# Precision_Singleboard_Leonardo_Charliepl.net
KiCad netlist of a schematic drawn in EAGLE
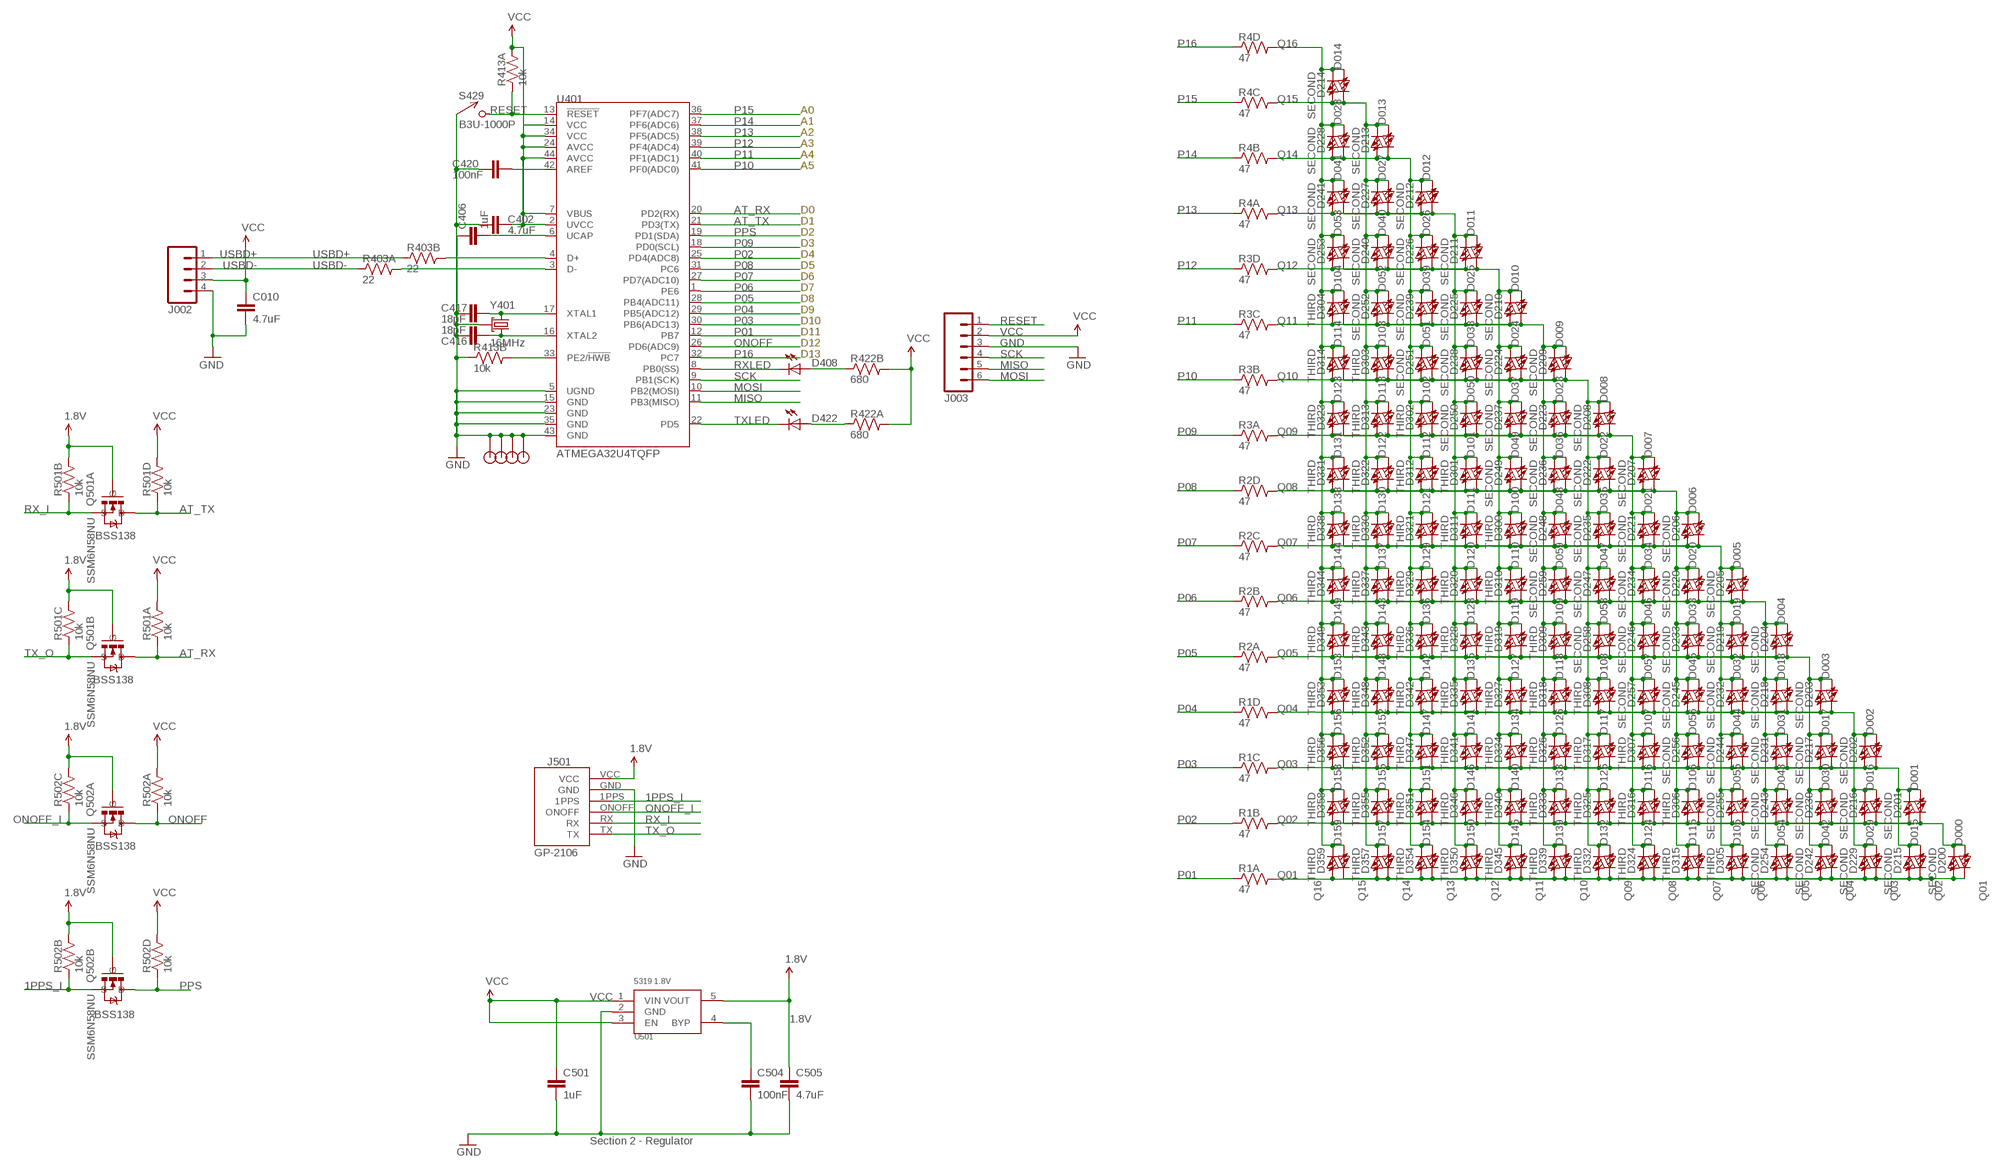
[diagram p0: schematic, sheet 1]

(export (version "E")
  (design (tool "Eeschema 10.0.6"))
  (components
    (comp (ref "C010")
      (value "4.7uF")
      (footprint "eagle-import:0603-CAP")
      (libsource (lib "eagle-import") (part "CAP0603-CAP"))
    )
    (comp (ref "C402")
      (value "4.7uF")
      (footprint "eagle-import:0603-CAP")
      (libsource (lib "eagle-import") (part "CAP0603-CAP"))
    )
    (comp (ref "C406")
      (value "1uF")
      (footprint "eagle-import:0603-CAP")
      (libsource (lib "eagle-import") (part "SparkFun-Passives_CAP0603-CAP"))
    )
    (comp (ref "C416")
      (value "18pF")
      (footprint "eagle-import:0603-CAP")
      (libsource (lib "eagle-import") (part "CAP0603-CAP"))
    )
    (comp (ref "C417")
      (value "18pF")
      (footprint "eagle-import:0603-CAP")
      (libsource (lib "eagle-import") (part "CAP0603-CAP"))
    )
    (comp (ref "C420")
      (value "100nF")
      (footprint "eagle-import:0603-CAP")
      (libsource (lib "eagle-import") (part "CAP0603-CAP"))
    )
    (comp (ref "C501")
      (value "1uF")
      (footprint "eagle-import:0603-CAP")
      (libsource (lib "eagle-import") (part "SparkFun-Passives_CAP0603-CAP"))
    )
    (comp (ref "C504")
      (value "100nF")
      (footprint "eagle-import:0603-CAP")
      (libsource (lib "eagle-import") (part "SparkFun-Passives_CAP0603-CAP"))
    )
    (comp (ref "C505")
      (value "4.7uF")
      (footprint "eagle-import:0603-CAP")
      (libsource (lib "eagle-import") (part "SparkFun-Passives_CAP0603-CAP"))
    )
    (comp (ref "D000")
      (value "HOUR")
      (footprint "eagle-import:LED-0603")
      (libsource (lib "eagle-import") (part "LED0603"))
    )
    (comp (ref "D001")
      (value "HOUR")
      (footprint "eagle-import:LED-0603")
      (libsource (lib "eagle-import") (part "LED0603"))
    )
    (comp (ref "D002")
      (value "HOUR")
      (footprint "eagle-import:LED-0603")
      (libsource (lib "eagle-import") (part "LED0603"))
    )
    (comp (ref "D003")
      (value "HOUR")
      (footprint "eagle-import:LED-0603")
      (libsource (lib "eagle-import") (part "LED0603"))
    )
    (comp (ref "D004")
      (value "HOUR")
      (footprint "eagle-import:LED-0603")
      (libsource (lib "eagle-import") (part "LED0603"))
    )
    (comp (ref "D005")
      (value "HOUR")
      (footprint "eagle-import:LED-0603")
      (libsource (lib "eagle-import") (part "LED0603"))
    )
    (comp (ref "D006")
      (value "HOUR")
      (footprint "eagle-import:LED-0603")
      (libsource (lib "eagle-import") (part "LED0603"))
    )
    (comp (ref "D007")
      (value "HOUR")
      (footprint "eagle-import:LED-0603")
      (libsource (lib "eagle-import") (part "LED0603"))
    )
    (comp (ref "D008")
      (value "HOUR")
      (footprint "eagle-import:LED-0603")
      (libsource (lib "eagle-import") (part "LED0603"))
    )
    (comp (ref "D009")
      (value "HOUR")
      (footprint "eagle-import:LED-0603")
      (libsource (lib "eagle-import") (part "LED0603"))
    )
    (comp (ref "D010")
      (value "HOUR")
      (footprint "eagle-import:LED-0603")
      (libsource (lib "eagle-import") (part "LED0603"))
    )
    (comp (ref "D011")
      (value "HOUR")
      (footprint "eagle-import:LED-0603")
      (libsource (lib "eagle-import") (part "LED0603"))
    )
    (comp (ref "D012")
      (value "HOUR")
      (footprint "eagle-import:LED-0603")
      (libsource (lib "eagle-import") (part "LED0603"))
    )
    (comp (ref "D013")
      (value "HOUR")
      (footprint "eagle-import:LED-0603")
      (libsource (lib "eagle-import") (part "LED0603"))
    )
    (comp (ref "D014")
      (value "HOUR")
      (footprint "eagle-import:LED-0603")
      (libsource (lib "eagle-import") (part "LED0603"))
    )
    (comp (ref "D015")
      (value "HOUR")
      (footprint "eagle-import:LED-0603")
      (libsource (lib "eagle-import") (part "LED0603"))
    )
    (comp (ref "D016")
      (value "HOUR")
      (footprint "eagle-import:LED-0603")
      (libsource (lib "eagle-import") (part "LED0603"))
    )
    (comp (ref "D017")
      (value "HOUR")
      (footprint "eagle-import:LED-0603")
      (libsource (lib "eagle-import") (part "LED0603"))
    )
    (comp (ref "D018")
      (value "HOUR")
      (footprint "eagle-import:LED-0603")
      (libsource (lib "eagle-import") (part "LED0603"))
    )
    (comp (ref "D019")
      (value "HOUR")
      (footprint "eagle-import:LED-0603")
      (libsource (lib "eagle-import") (part "LED0603"))
    )
    (comp (ref "D020")
      (value "HOUR")
      (footprint "eagle-import:LED-0603")
      (libsource (lib "eagle-import") (part "LED0603"))
    )
    (comp (ref "D021")
      (value "HOUR")
      (footprint "eagle-import:LED-0603")
      (libsource (lib "eagle-import") (part "LED0603"))
    )
    (comp (ref "D022")
      (value "HOUR")
      (footprint "eagle-import:LED-0603")
      (libsource (lib "eagle-import") (part "LED0603"))
    )
    (comp (ref "D023")
      (value "HOUR")
      (footprint "eagle-import:LED-0603")
      (libsource (lib "eagle-import") (part "LED0603"))
    )
    (comp (ref "D024")
      (value "HOUR")
      (footprint "eagle-import:LED-0603")
      (libsource (lib "eagle-import") (part "LED0603"))
    )
    (comp (ref "D025")
      (value "HOUR")
      (footprint "eagle-import:LED-0603")
      (libsource (lib "eagle-import") (part "LED0603"))
    )
    (comp (ref "D026")
      (value "HOUR")
      (footprint "eagle-import:LED-0603")
      (libsource (lib "eagle-import") (part "LED0603"))
    )
    (comp (ref "D027")
      (value "HOUR")
      (footprint "eagle-import:LED-0603")
      (libsource (lib "eagle-import") (part "LED0603"))
    )
    (comp (ref "D028")
      (value "HOUR")
      (footprint "eagle-import:LED-0603")
      (libsource (lib "eagle-import") (part "LED0603"))
    )
    (comp (ref "D029")
      (value "HOUR")
      (footprint "eagle-import:LED-0603")
      (libsource (lib "eagle-import") (part "LED0603"))
    )
    (comp (ref "D030")
      (value "HOUR")
      (footprint "eagle-import:LED-0603")
      (libsource (lib "eagle-import") (part "LED0603"))
    )
    (comp (ref "D031")
      (value "HOUR")
      (footprint "eagle-import:LED-0603")
      (libsource (lib "eagle-import") (part "LED0603"))
    )
    (comp (ref "D032")
      (value "HOUR")
      (footprint "eagle-import:LED-0603")
      (libsource (lib "eagle-import") (part "LED0603"))
    )
    (comp (ref "D033")
      (value "HOUR")
      (footprint "eagle-import:LED-0603")
      (libsource (lib "eagle-import") (part "LED0603"))
    )
    (comp (ref "D034")
      (value "HOUR")
      (footprint "eagle-import:LED-0603")
      (libsource (lib "eagle-import") (part "LED0603"))
    )
    (comp (ref "D035")
      (value "HOUR")
      (footprint "eagle-import:LED-0603")
      (libsource (lib "eagle-import") (part "LED0603"))
    )
    (comp (ref "D036")
      (value "HOUR")
      (footprint "eagle-import:LED-0603")
      (libsource (lib "eagle-import") (part "LED0603"))
    )
    (comp (ref "D037")
      (value "HOUR")
      (footprint "eagle-import:LED-0603")
      (libsource (lib "eagle-import") (part "LED0603"))
    )
    (comp (ref "D038")
      (value "HOUR")
      (footprint "eagle-import:LED-0603")
      (libsource (lib "eagle-import") (part "LED0603"))
    )
    (comp (ref "D039")
      (value "HOUR")
      (footprint "eagle-import:LED-0603")
      (libsource (lib "eagle-import") (part "LED0603"))
    )
    (comp (ref "D040")
      (value "HOUR")
      (footprint "eagle-import:LED-0603")
      (libsource (lib "eagle-import") (part "LED0603"))
    )
    (comp (ref "D041")
      (value "HOUR")
      (footprint "eagle-import:LED-0603")
      (libsource (lib "eagle-import") (part "LED0603"))
    )
    (comp (ref "D042")
      (value "HOUR")
      (footprint "eagle-import:LED-0603")
      (libsource (lib "eagle-import") (part "LED0603"))
    )
    (comp (ref "D043")
      (value "HOUR")
      (footprint "eagle-import:LED-0603")
      (libsource (lib "eagle-import") (part "LED0603"))
    )
    (comp (ref "D044")
      (value "HOUR")
      (footprint "eagle-import:LED-0603")
      (libsource (lib "eagle-import") (part "LED0603"))
    )
    (comp (ref "D045")
      (value "HOUR")
      (footprint "eagle-import:LED-0603")
      (libsource (lib "eagle-import") (part "LED0603"))
    )
    (comp (ref "D046")
      (value "HOUR")
      (footprint "eagle-import:LED-0603")
      (libsource (lib "eagle-import") (part "LED0603"))
    )
    (comp (ref "D047")
      (value "HOUR")
      (footprint "eagle-import:LED-0603")
      (libsource (lib "eagle-import") (part "LED0603"))
    )
    (comp (ref "D048")
      (value "HOUR")
      (footprint "eagle-import:LED-0603")
      (libsource (lib "eagle-import") (part "LED0603"))
    )
    (comp (ref "D049")
      (value "HOUR")
      (footprint "eagle-import:LED-0603")
      (libsource (lib "eagle-import") (part "LED0603"))
    )
    (comp (ref "D050")
      (value "HOUR")
      (footprint "eagle-import:LED-0603")
      (libsource (lib "eagle-import") (part "LED0603"))
    )
    (comp (ref "D051")
      (value "HOUR")
      (footprint "eagle-import:LED-0603")
      (libsource (lib "eagle-import") (part "LED0603"))
    )
    (comp (ref "D052")
      (value "HOUR")
      (footprint "eagle-import:LED-0603")
      (libsource (lib "eagle-import") (part "LED0603"))
    )
    (comp (ref "D053")
      (value "HOUR")
      (footprint "eagle-import:LED-0603")
      (libsource (lib "eagle-import") (part "LED0603"))
    )
    (comp (ref "D054")
      (value "HOUR")
      (footprint "eagle-import:LED-0603")
      (libsource (lib "eagle-import") (part "LED0603"))
    )
    (comp (ref "D055")
      (value "HOUR")
      (footprint "eagle-import:LED-0603")
      (libsource (lib "eagle-import") (part "LED0603"))
    )
    (comp (ref "D056")
      (value "HOUR")
      (footprint "eagle-import:LED-0603")
      (libsource (lib "eagle-import") (part "LED0603"))
    )
    (comp (ref "D057")
      (value "HOUR")
      (footprint "eagle-import:LED-0603")
      (libsource (lib "eagle-import") (part "LED0603"))
    )
    (comp (ref "D058")
      (value "HOUR")
      (footprint "eagle-import:LED-0603")
      (libsource (lib "eagle-import") (part "LED0603"))
    )
    (comp (ref "D059")
      (value "HOUR")
      (footprint "eagle-import:LED-0603")
      (libsource (lib "eagle-import") (part "LED0603"))
    )
    (comp (ref "D100")
      (value "MINUTE")
      (footprint "eagle-import:LED-0603")
      (libsource (lib "eagle-import") (part "LED0603"))
    )
    (comp (ref "D101")
      (value "MINUTE")
      (footprint "eagle-import:LED-0603")
      (libsource (lib "eagle-import") (part "LED0603"))
    )
    (comp (ref "D102")
      (value "MINUTE")
      (footprint "eagle-import:LED-0603")
      (libsource (lib "eagle-import") (part "LED0603"))
    )
    (comp (ref "D103")
      (value "MINUTE")
      (footprint "eagle-import:LED-0603")
      (libsource (lib "eagle-import") (part "LED0603"))
    )
    (comp (ref "D104")
      (value "MINUTE")
      (footprint "eagle-import:LED-0603")
      (libsource (lib "eagle-import") (part "LED0603"))
    )
    (comp (ref "D105")
      (value "MINUTE")
      (footprint "eagle-import:LED-0603")
      (libsource (lib "eagle-import") (part "LED0603"))
    )
    (comp (ref "D106")
      (value "MINUTE")
      (footprint "eagle-import:LED-0603")
      (libsource (lib "eagle-import") (part "LED0603"))
    )
    (comp (ref "D107")
      (value "MINUTE")
      (footprint "eagle-import:LED-0603")
      (libsource (lib "eagle-import") (part "LED0603"))
    )
    (comp (ref "D108")
      (value "MINUTE")
      (footprint "eagle-import:LED-0603")
      (libsource (lib "eagle-import") (part "LED0603"))
    )
    (comp (ref "D109")
      (value "MINUTE")
      (footprint "eagle-import:LED-0603")
      (libsource (lib "eagle-import") (part "LED0603"))
    )
    (comp (ref "D110")
      (value "MINUTE")
      (footprint "eagle-import:LED-0603")
      (libsource (lib "eagle-import") (part "LED0603"))
    )
    (comp (ref "D111")
      (value "MINUTE")
      (footprint "eagle-import:LED-0603")
      (libsource (lib "eagle-import") (part "LED0603"))
    )
    (comp (ref "D112")
      (value "MINUTE")
      (footprint "eagle-import:LED-0603")
      (libsource (lib "eagle-import") (part "LED0603"))
    )
    (comp (ref "D113")
      (value "MINUTE")
      (footprint "eagle-import:LED-0603")
      (libsource (lib "eagle-import") (part "LED0603"))
    )
    (comp (ref "D114")
      (value "MINUTE")
      (footprint "eagle-import:LED-0603")
      (libsource (lib "eagle-import") (part "LED0603"))
    )
    (comp (ref "D115")
      (value "MINUTE")
      (footprint "eagle-import:LED-0603")
      (libsource (lib "eagle-import") (part "LED0603"))
    )
    (comp (ref "D116")
      (value "MINUTE")
      (footprint "eagle-import:LED-0603")
      (libsource (lib "eagle-import") (part "LED0603"))
    )
    (comp (ref "D117")
      (value "MINUTE")
      (footprint "eagle-import:LED-0603")
      (libsource (lib "eagle-import") (part "LED0603"))
    )
    (comp (ref "D118")
      (value "MINUTE")
      (footprint "eagle-import:LED-0603")
      (libsource (lib "eagle-import") (part "LED0603"))
    )
    (comp (ref "D119")
      (value "MINUTE")
      (footprint "eagle-import:LED-0603")
      (libsource (lib "eagle-import") (part "LED0603"))
    )
    (comp (ref "D120")
      (value "MINUTE")
      (footprint "eagle-import:LED-0603")
      (libsource (lib "eagle-import") (part "LED0603"))
    )
    (comp (ref "D121")
      (value "MINUTE")
      (footprint "eagle-import:LED-0603")
      (libsource (lib "eagle-import") (part "LED0603"))
    )
    (comp (ref "D122")
      (value "MINUTE")
      (footprint "eagle-import:LED-0603")
      (libsource (lib "eagle-import") (part "LED0603"))
    )
    (comp (ref "D123")
      (value "MINUTE")
      (footprint "eagle-import:LED-0603")
      (libsource (lib "eagle-import") (part "LED0603"))
    )
    (comp (ref "D124")
      (value "MINUTE")
      (footprint "eagle-import:LED-0603")
      (libsource (lib "eagle-import") (part "LED0603"))
    )
    (comp (ref "D125")
      (value "MINUTE")
      (footprint "eagle-import:LED-0603")
      (libsource (lib "eagle-import") (part "LED0603"))
    )
    (comp (ref "D126")
      (value "MINUTE")
      (footprint "eagle-import:LED-0603")
      (libsource (lib "eagle-import") (part "LED0603"))
    )
    (comp (ref "D127")
      (value "MINUTE")
      (footprint "eagle-import:LED-0603")
      (libsource (lib "eagle-import") (part "LED0603"))
    )
    (comp (ref "D128")
      (value "MINUTE")
      (footprint "eagle-import:LED-0603")
      (libsource (lib "eagle-import") (part "LED0603"))
    )
    (comp (ref "D129")
      (value "MINUTE")
      (footprint "eagle-import:LED-0603")
      (libsource (lib "eagle-import") (part "LED0603"))
    )
    (comp (ref "D130")
      (value "MINUTE")
      (footprint "eagle-import:LED-0603")
      (libsource (lib "eagle-import") (part "LED0603"))
    )
    (comp (ref "D131")
      (value "MINUTE")
      (footprint "eagle-import:LED-0603")
      (libsource (lib "eagle-import") (part "LED0603"))
    )
    (comp (ref "D132")
      (value "MINUTE")
      (footprint "eagle-import:LED-0603")
      (libsource (lib "eagle-import") (part "LED0603"))
    )
    (comp (ref "D133")
      (value "MINUTE")
      (footprint "eagle-import:LED-0603")
      (libsource (lib "eagle-import") (part "LED0603"))
    )
    (comp (ref "D134")
      (value "MINUTE")
      (footprint "eagle-import:LED-0603")
      (libsource (lib "eagle-import") (part "LED0603"))
    )
    (comp (ref "D135")
      (value "MINUTE")
      (footprint "eagle-import:LED-0603")
      (libsource (lib "eagle-import") (part "LED0603"))
    )
    (comp (ref "D136")
      (value "MINUTE")
      (footprint "eagle-import:LED-0603")
      (libsource (lib "eagle-import") (part "LED0603"))
    )
    (comp (ref "D137")
      (value "MINUTE")
      (footprint "eagle-import:LED-0603")
      (libsource (lib "eagle-import") (part "LED0603"))
    )
    (comp (ref "D138")
      (value "MINUTE")
      (footprint "eagle-import:LED-0603")
      (libsource (lib "eagle-import") (part "LED0603"))
    )
    (comp (ref "D139")
      (value "MINUTE")
      (footprint "eagle-import:LED-0603")
      (libsource (lib "eagle-import") (part "LED0603"))
    )
    (comp (ref "D140")
      (value "MINUTE")
      (footprint "eagle-import:LED-0603")
      (libsource (lib "eagle-import") (part "LED0603"))
    )
    (comp (ref "D141")
      (value "MINUTE")
      (footprint "eagle-import:LED-0603")
      (libsource (lib "eagle-import") (part "LED0603"))
    )
    (comp (ref "D142")
      (value "MINUTE")
      (footprint "eagle-import:LED-0603")
      (libsource (lib "eagle-import") (part "LED0603"))
    )
    (comp (ref "D143")
      (value "MINUTE")
      (footprint "eagle-import:LED-0603")
      (libsource (lib "eagle-import") (part "LED0603"))
    )
    (comp (ref "D144")
      (value "MINUTE")
      (footprint "eagle-import:LED-0603")
      (libsource (lib "eagle-import") (part "LED0603"))
    )
    (comp (ref "D145")
      (value "MINUTE")
      (footprint "eagle-import:LED-0603")
      (libsource (lib "eagle-import") (part "LED0603"))
    )
    (comp (ref "D146")
      (value "MINUTE")
      (footprint "eagle-import:LED-0603")
      (libsource (lib "eagle-import") (part "LED0603"))
    )
    (comp (ref "D147")
      (value "MINUTE")
      (footprint "eagle-import:LED-0603")
      (libsource (lib "eagle-import") (part "LED0603"))
    )
    (comp (ref "D148")
      (value "MINUTE")
      (footprint "eagle-import:LED-0603")
      (libsource (lib "eagle-import") (part "LED0603"))
    )
    (comp (ref "D149")
      (value "MINUTE")
      (footprint "eagle-import:LED-0603")
      (libsource (lib "eagle-import") (part "LED0603"))
    )
    (comp (ref "D150")
      (value "MINUTE")
      (footprint "eagle-import:LED-0603")
      (libsource (lib "eagle-import") (part "LED0603"))
    )
    (comp (ref "D151")
      (value "MINUTE")
      (footprint "eagle-import:LED-0603")
      (libsource (lib "eagle-import") (part "LED0603"))
    )
    (comp (ref "D152")
      (value "MINUTE")
      (footprint "eagle-import:LED-0603")
      (libsource (lib "eagle-import") (part "LED0603"))
    )
    (comp (ref "D153")
      (value "MINUTE")
      (footprint "eagle-import:LED-0603")
      (libsource (lib "eagle-import") (part "LED0603"))
    )
    (comp (ref "D154")
      (value "MINUTE")
      (footprint "eagle-import:LED-0603")
      (libsource (lib "eagle-import") (part "LED0603"))
    )
    (comp (ref "D155")
      (value "MINUTE")
      (footprint "eagle-import:LED-0603")
      (libsource (lib "eagle-import") (part "LED0603"))
    )
    (comp (ref "D156")
      (value "MINUTE")
      (footprint "eagle-import:LED-0603")
      (libsource (lib "eagle-import") (part "LED0603"))
    )
    (comp (ref "D157")
      (value "MINUTE")
      (footprint "eagle-import:LED-0603")
      (libsource (lib "eagle-import") (part "LED0603"))
    )
    (comp (ref "D158")
      (value "MINUTE")
      (footprint "eagle-import:LED-0603")
      (libsource (lib "eagle-import") (part "LED0603"))
    )
    (comp (ref "D159")
      (value "MINUTE")
      (footprint "eagle-import:LED-0603")
      (libsource (lib "eagle-import") (part "LED0603"))
    )
    (comp (ref "D200")
      (value "SECOND")
      (footprint "eagle-import:LED-0603")
      (libsource (lib "eagle-import") (part "SparkFun-LED_LED0603"))
    )
    (comp (ref "D201")
      (value "SECOND")
      (footprint "eagle-import:LED-0603")
      (libsource (lib "eagle-import") (part "SparkFun-LED_LED0603"))
    )
    (comp (ref "D202")
      (value "SECOND")
      (footprint "eagle-import:LED-0603")
      (libsource (lib "eagle-import") (part "SparkFun-LED_LED0603"))
    )
    (comp (ref "D203")
      (value "SECOND")
      (footprint "eagle-import:LED-0603")
      (libsource (lib "eagle-import") (part "SparkFun-LED_LED0603"))
    )
    (comp (ref "D204")
      (value "SECOND")
      (footprint "eagle-import:LED-0603")
      (libsource (lib "eagle-import") (part "SparkFun-LED_LED0603"))
    )
    (comp (ref "D205")
      (value "SECOND")
      (footprint "eagle-import:LED-0603")
      (libsource (lib "eagle-import") (part "SparkFun-LED_LED0603"))
    )
    (comp (ref "D206")
      (value "SECOND")
      (footprint "eagle-import:LED-0603")
      (libsource (lib "eagle-import") (part "SparkFun-LED_LED0603"))
    )
    (comp (ref "D207")
      (value "SECOND")
      (footprint "eagle-import:LED-0603")
      (libsource (lib "eagle-import") (part "SparkFun-LED_LED0603"))
    )
    (comp (ref "D208")
      (value "SECOND")
      (footprint "eagle-import:LED-0603")
      (libsource (lib "eagle-import") (part "SparkFun-LED_LED0603"))
    )
    (comp (ref "D209")
      (value "SECOND")
      (footprint "eagle-import:LED-0603")
      (libsource (lib "eagle-import") (part "SparkFun-LED_LED0603"))
    )
    (comp (ref "D210")
      (value "SECOND")
      (footprint "eagle-import:LED-0603")
      (libsource (lib "eagle-import") (part "SparkFun-LED_LED0603"))
    )
    (comp (ref "D211")
      (value "SECOND")
      (footprint "eagle-import:LED-0603")
      (libsource (lib "eagle-import") (part "SparkFun-LED_LED0603"))
    )
    (comp (ref "D212")
      (value "SECOND")
      (footprint "eagle-import:LED-0603")
      (libsource (lib "eagle-import") (part "SparkFun-LED_LED0603"))
    )
    (comp (ref "D213")
      (value "SECOND")
      (footprint "eagle-import:LED-0603")
      (libsource (lib "eagle-import") (part "SparkFun-LED_LED0603"))
    )
    (comp (ref "D214")
      (value "SECOND")
      (footprint "eagle-import:LED-0603")
      (libsource (lib "eagle-import") (part "SparkFun-LED_LED0603"))
    )
    (comp (ref "D215")
      (value "SECOND")
      (footprint "eagle-import:LED-0603")
      (libsource (lib "eagle-import") (part "SparkFun-LED_LED0603"))
    )
    (comp (ref "D216")
      (value "SECOND")
      (footprint "eagle-import:LED-0603")
      (libsource (lib "eagle-import") (part "SparkFun-LED_LED0603"))
    )
    (comp (ref "D217")
      (value "SECOND")
      (footprint "eagle-import:LED-0603")
      (libsource (lib "eagle-import") (part "SparkFun-LED_LED0603"))
    )
    (comp (ref "D218")
      (value "SECOND")
      (footprint "eagle-import:LED-0603")
      (libsource (lib "eagle-import") (part "SparkFun-LED_LED0603"))
    )
    (comp (ref "D219")
      (value "SECOND")
      (footprint "eagle-import:LED-0603")
      (libsource (lib "eagle-import") (part "SparkFun-LED_LED0603"))
    )
    (comp (ref "D220")
      (value "SECOND")
      (footprint "eagle-import:LED-0603")
      (libsource (lib "eagle-import") (part "SparkFun-LED_LED0603"))
    )
    (comp (ref "D221")
      (value "SECOND")
      (footprint "eagle-import:LED-0603")
      (libsource (lib "eagle-import") (part "SparkFun-LED_LED0603"))
    )
    (comp (ref "D222")
      (value "SECOND")
      (footprint "eagle-import:LED-0603")
      (libsource (lib "eagle-import") (part "SparkFun-LED_LED0603"))
    )
    (comp (ref "D223")
      (value "SECOND")
      (footprint "eagle-import:LED-0603")
      (libsource (lib "eagle-import") (part "SparkFun-LED_LED0603"))
    )
    (comp (ref "D224")
      (value "SECOND")
      (footprint "eagle-import:LED-0603")
      (libsource (lib "eagle-import") (part "SparkFun-LED_LED0603"))
    )
    (comp (ref "D225")
      (value "SECOND")
      (footprint "eagle-import:LED-0603")
      (libsource (lib "eagle-import") (part "SparkFun-LED_LED0603"))
    )
    (comp (ref "D226")
      (value "SECOND")
      (footprint "eagle-import:LED-0603")
      (libsource (lib "eagle-import") (part "SparkFun-LED_LED0603"))
    )
    (comp (ref "D227")
      (value "SECOND")
      (footprint "eagle-import:LED-0603")
      (libsource (lib "eagle-import") (part "SparkFun-LED_LED0603"))
    )
    (comp (ref "D228")
      (value "SECOND")
      (footprint "eagle-import:LED-0603")
      (libsource (lib "eagle-import") (part "SparkFun-LED_LED0603"))
    )
    (comp (ref "D229")
      (value "SECOND")
      (footprint "eagle-import:LED-0603")
      (libsource (lib "eagle-import") (part "SparkFun-LED_LED0603"))
    )
    (comp (ref "D230")
      (value "SECOND")
      (footprint "eagle-import:LED-0603")
      (libsource (lib "eagle-import") (part "SparkFun-LED_LED0603"))
    )
    (comp (ref "D231")
      (value "SECOND")
      (footprint "eagle-import:LED-0603")
      (libsource (lib "eagle-import") (part "SparkFun-LED_LED0603"))
    )
    (comp (ref "D232")
      (value "SECOND")
      (footprint "eagle-import:LED-0603")
      (libsource (lib "eagle-import") (part "SparkFun-LED_LED0603"))
    )
    (comp (ref "D233")
      (value "SECOND")
      (footprint "eagle-import:LED-0603")
      (libsource (lib "eagle-import") (part "SparkFun-LED_LED0603"))
    )
    (comp (ref "D234")
      (value "SECOND")
      (footprint "eagle-import:LED-0603")
      (libsource (lib "eagle-import") (part "SparkFun-LED_LED0603"))
    )
    (comp (ref "D235")
      (value "SECOND")
      (footprint "eagle-import:LED-0603")
      (libsource (lib "eagle-import") (part "SparkFun-LED_LED0603"))
    )
    (comp (ref "D236")
      (value "SECOND")
      (footprint "eagle-import:LED-0603")
      (libsource (lib "eagle-import") (part "SparkFun-LED_LED0603"))
    )
    (comp (ref "D237")
      (value "SECOND")
      (footprint "eagle-import:LED-0603")
      (libsource (lib "eagle-import") (part "SparkFun-LED_LED0603"))
    )
    (comp (ref "D238")
      (value "SECOND")
      (footprint "eagle-import:LED-0603")
      (libsource (lib "eagle-import") (part "SparkFun-LED_LED0603"))
    )
    (comp (ref "D239")
      (value "SECOND")
      (footprint "eagle-import:LED-0603")
      (libsource (lib "eagle-import") (part "SparkFun-LED_LED0603"))
    )
    (comp (ref "D240")
      (value "SECOND")
      (footprint "eagle-import:LED-0603")
      (libsource (lib "eagle-import") (part "SparkFun-LED_LED0603"))
    )
    (comp (ref "D241")
      (value "SECOND")
      (footprint "eagle-import:LED-0603")
      (libsource (lib "eagle-import") (part "LED0603"))
    )
    (comp (ref "D242")
      (value "SECOND")
      (footprint "eagle-import:LED-0603")
      (libsource (lib "eagle-import") (part "SparkFun-LED_LED0603"))
    )
    (comp (ref "D243")
      (value "SECOND")
      (footprint "eagle-import:LED-0603")
      (libsource (lib "eagle-import") (part "SparkFun-LED_LED0603"))
    )
    (comp (ref "D244")
      (value "SECOND")
      (footprint "eagle-import:LED-0603")
      (libsource (lib "eagle-import") (part "SparkFun-LED_LED0603"))
    )
    (comp (ref "D245")
      (value "SECOND")
      (footprint "eagle-import:LED-0603")
      (libsource (lib "eagle-import") (part "SparkFun-LED_LED0603"))
    )
    (comp (ref "D246")
      (value "SECOND")
      (footprint "eagle-import:LED-0603")
      (libsource (lib "eagle-import") (part "SparkFun-LED_LED0603"))
    )
    (comp (ref "D247")
      (value "SECOND")
      (footprint "eagle-import:LED-0603")
      (libsource (lib "eagle-import") (part "SparkFun-LED_LED0603"))
    )
    (comp (ref "D248")
      (value "SECOND")
      (footprint "eagle-import:LED-0603")
      (libsource (lib "eagle-import") (part "SparkFun-LED_LED0603"))
    )
    (comp (ref "D249")
      (value "SECOND")
      (footprint "eagle-import:LED-0603")
      (libsource (lib "eagle-import") (part "SparkFun-LED_LED0603"))
    )
    (comp (ref "D250")
      (value "SECOND")
      (footprint "eagle-import:LED-0603")
      (libsource (lib "eagle-import") (part "SparkFun-LED_LED0603"))
    )
    (comp (ref "D251")
      (value "SECOND")
      (footprint "eagle-import:LED-0603")
      (libsource (lib "eagle-import") (part "SparkFun-LED_LED0603"))
    )
    (comp (ref "D252")
      (value "SECOND")
      (footprint "eagle-import:LED-0603")
      (libsource (lib "eagle-import") (part "SparkFun-LED_LED0603"))
    )
    (comp (ref "D253")
      (value "SECOND")
      (footprint "eagle-import:LED-0603")
      (libsource (lib "eagle-import") (part "SparkFun-LED_LED0603"))
    )
    (comp (ref "D254")
      (value "SECOND")
      (footprint "eagle-import:LED-0603")
      (libsource (lib "eagle-import") (part "SparkFun-LED_LED0603"))
    )
    (comp (ref "D255")
      (value "SECOND")
      (footprint "eagle-import:LED-0603")
      (libsource (lib "eagle-import") (part "SparkFun-LED_LED0603"))
    )
    (comp (ref "D256")
      (value "SECOND")
      (footprint "eagle-import:LED-0603")
      (libsource (lib "eagle-import") (part "SparkFun-LED_LED0603"))
    )
    (comp (ref "D257")
      (value "SECOND")
      (footprint "eagle-import:LED-0603")
      (libsource (lib "eagle-import") (part "SparkFun-LED_LED0603"))
    )
    (comp (ref "D258")
      (value "SECOND")
      (footprint "eagle-import:LED-0603")
      (libsource (lib "eagle-import") (part "SparkFun-LED_LED0603"))
    )
    (comp (ref "D259")
      (value "SECOND")
      (footprint "eagle-import:LED-0603")
      (libsource (lib "eagle-import") (part "SparkFun-LED_LED0603"))
    )
    (comp (ref "D300")
      (value "THIRD")
      (footprint "eagle-import:LED-0603")
      (libsource (lib "eagle-import") (part "SparkFun-LED_LED0603"))
    )
    (comp (ref "D301")
      (value "THIRD")
      (footprint "eagle-import:LED-0603")
      (libsource (lib "eagle-import") (part "SparkFun-LED_LED0603"))
    )
    (comp (ref "D302")
      (value "THIRD")
      (footprint "eagle-import:LED-0603")
      (libsource (lib "eagle-import") (part "SparkFun-LED_LED0603"))
    )
    (comp (ref "D303")
      (value "THIRD")
      (footprint "eagle-import:LED-0603")
      (libsource (lib "eagle-import") (part "SparkFun-LED_LED0603"))
    )
    (comp (ref "D304")
      (value "THIRD")
      (footprint "eagle-import:LED-0603")
      (libsource (lib "eagle-import") (part "SparkFun-LED_LED0603"))
    )
    (comp (ref "D305")
      (value "THIRD")
      (footprint "eagle-import:LED-0603")
      (libsource (lib "eagle-import") (part "SparkFun-LED_LED0603"))
    )
    (comp (ref "D306")
      (value "THIRD")
      (footprint "eagle-import:LED-0603")
      (libsource (lib "eagle-import") (part "SparkFun-LED_LED0603"))
    )
    (comp (ref "D307")
      (value "THIRD")
      (footprint "eagle-import:LED-0603")
      (libsource (lib "eagle-import") (part "SparkFun-LED_LED0603"))
    )
    (comp (ref "D308")
      (value "THIRD")
      (footprint "eagle-import:LED-0603")
      (libsource (lib "eagle-import") (part "SparkFun-LED_LED0603"))
    )
    (comp (ref "D309")
      (value "THIRD")
      (footprint "eagle-import:LED-0603")
      (libsource (lib "eagle-import") (part "SparkFun-LED_LED0603"))
    )
    (comp (ref "D310")
      (value "THIRD")
      (footprint "eagle-import:LED-0603")
      (libsource (lib "eagle-import") (part "SparkFun-LED_LED0603"))
    )
    (comp (ref "D311")
      (value "THIRD")
      (footprint "eagle-import:LED-0603")
      (libsource (lib "eagle-import") (part "SparkFun-LED_LED0603"))
    )
    (comp (ref "D312")
      (value "THIRD")
      (footprint "eagle-import:LED-0603")
      (libsource (lib "eagle-import") (part "SparkFun-LED_LED0603"))
    )
    (comp (ref "D313")
      (value "THIRD")
      (footprint "eagle-import:LED-0603")
      (libsource (lib "eagle-import") (part "SparkFun-LED_LED0603"))
    )
    (comp (ref "D314")
      (value "THIRD")
      (footprint "eagle-import:LED-0603")
      (libsource (lib "eagle-import") (part "SparkFun-LED_LED0603"))
    )
    (comp (ref "D315")
      (value "THIRD")
      (footprint "eagle-import:LED-0603")
      (libsource (lib "eagle-import") (part "SparkFun-LED_LED0603"))
    )
    (comp (ref "D316")
      (value "THIRD")
      (footprint "eagle-import:LED-0603")
      (libsource (lib "eagle-import") (part "SparkFun-LED_LED0603"))
    )
    (comp (ref "D317")
      (value "THIRD")
      (footprint "eagle-import:LED-0603")
      (libsource (lib "eagle-import") (part "SparkFun-LED_LED0603"))
    )
    (comp (ref "D318")
      (value "THIRD")
      (footprint "eagle-import:LED-0603")
      (libsource (lib "eagle-import") (part "SparkFun-LED_LED0603"))
    )
    (comp (ref "D319")
      (value "THIRD")
      (footprint "eagle-import:LED-0603")
      (libsource (lib "eagle-import") (part "SparkFun-LED_LED0603"))
    )
    (comp (ref "D320")
      (value "THIRD")
      (footprint "eagle-import:LED-0603")
      (libsource (lib "eagle-import") (part "SparkFun-LED_LED0603"))
    )
    (comp (ref "D321")
      (value "THIRD")
      (footprint "eagle-import:LED-0603")
      (libsource (lib "eagle-import") (part "SparkFun-LED_LED0603"))
    )
    (comp (ref "D322")
      (value "THIRD")
      (footprint "eagle-import:LED-0603")
      (libsource (lib "eagle-import") (part "SparkFun-LED_LED0603"))
    )
    (comp (ref "D323")
      (value "THIRD")
      (footprint "eagle-import:LED-0603")
      (libsource (lib "eagle-import") (part "SparkFun-LED_LED0603"))
    )
    (comp (ref "D324")
      (value "THIRD")
      (footprint "eagle-import:LED-0603")
      (libsource (lib "eagle-import") (part "SparkFun-LED_LED0603"))
    )
    (comp (ref "D325")
      (value "THIRD")
      (footprint "eagle-import:LED-0603")
      (libsource (lib "eagle-import") (part "SparkFun-LED_LED0603"))
    )
    (comp (ref "D326")
      (value "THIRD")
      (footprint "eagle-import:LED-0603")
      (libsource (lib "eagle-import") (part "SparkFun-LED_LED0603"))
    )
    (comp (ref "D327")
      (value "THIRD")
      (footprint "eagle-import:LED-0603")
      (libsource (lib "eagle-import") (part "SparkFun-LED_LED0603"))
    )
    (comp (ref "D328")
      (value "THIRD")
      (footprint "eagle-import:LED-0603")
      (libsource (lib "eagle-import") (part "SparkFun-LED_LED0603"))
    )
    (comp (ref "D329")
      (value "THIRD")
      (footprint "eagle-import:LED-0603")
      (libsource (lib "eagle-import") (part "SparkFun-LED_LED0603"))
    )
    (comp (ref "D330")
      (value "THIRD")
      (footprint "eagle-import:LED-0603")
      (libsource (lib "eagle-import") (part "SparkFun-LED_LED0603"))
    )
    (comp (ref "D331")
      (value "THIRD")
      (footprint "eagle-import:LED-0603")
      (libsource (lib "eagle-import") (part "SparkFun-LED_LED0603"))
    )
    (comp (ref "D332")
      (value "THIRD")
      (footprint "eagle-import:LED-0603")
      (libsource (lib "eagle-import") (part "SparkFun-LED_LED0603"))
    )
    (comp (ref "D333")
      (value "THIRD")
      (footprint "eagle-import:LED-0603")
      (libsource (lib "eagle-import") (part "SparkFun-LED_LED0603"))
    )
    (comp (ref "D334")
      (value "THIRD")
      (footprint "eagle-import:LED-0603")
      (libsource (lib "eagle-import") (part "SparkFun-LED_LED0603"))
    )
    (comp (ref "D335")
      (value "THIRD")
      (footprint "eagle-import:LED-0603")
      (libsource (lib "eagle-import") (part "SparkFun-LED_LED0603"))
    )
    (comp (ref "D336")
      (value "THIRD")
      (footprint "eagle-import:LED-0603")
      (libsource (lib "eagle-import") (part "SparkFun-LED_LED0603"))
    )
    (comp (ref "D337")
      (value "THIRD")
      (footprint "eagle-import:LED-0603")
      (libsource (lib "eagle-import") (part "SparkFun-LED_LED0603"))
    )
    (comp (ref "D338")
      (value "THIRD")
      (footprint "eagle-import:LED-0603")
      (libsource (lib "eagle-import") (part "SparkFun-LED_LED0603"))
    )
    (comp (ref "D339")
      (value "THIRD")
      (footprint "eagle-import:LED-0603")
      (libsource (lib "eagle-import") (part "SparkFun-LED_LED0603"))
    )
    (comp (ref "D340")
      (value "THIRD")
      (footprint "eagle-import:LED-0603")
      (libsource (lib "eagle-import") (part "SparkFun-LED_LED0603"))
    )
    (comp (ref "D341")
      (value "THIRD")
      (footprint "eagle-import:LED-0603")
      (libsource (lib "eagle-import") (part "SparkFun-LED_LED0603"))
    )
    (comp (ref "D342")
      (value "THIRD")
      (footprint "eagle-import:LED-0603")
      (libsource (lib "eagle-import") (part "SparkFun-LED_LED0603"))
    )
    (comp (ref "D343")
      (value "THIRD")
      (footprint "eagle-import:LED-0603")
      (libsource (lib "eagle-import") (part "SparkFun-LED_LED0603"))
    )
    (comp (ref "D344")
      (value "THIRD")
      (footprint "eagle-import:LED-0603")
      (libsource (lib "eagle-import") (part "SparkFun-LED_LED0603"))
    )
    (comp (ref "D345")
      (value "THIRD")
      (footprint "eagle-import:LED-0603")
      (libsource (lib "eagle-import") (part "SparkFun-LED_LED0603"))
    )
    (comp (ref "D346")
      (value "THIRD")
      (footprint "eagle-import:LED-0603")
      (libsource (lib "eagle-import") (part "SparkFun-LED_LED0603"))
    )
    (comp (ref "D347")
      (value "THIRD")
      (footprint "eagle-import:LED-0603")
      (libsource (lib "eagle-import") (part "SparkFun-LED_LED0603"))
    )
    (comp (ref "D348")
      (value "THIRD")
      (footprint "eagle-import:LED-0603")
      (libsource (lib "eagle-import") (part "SparkFun-LED_LED0603"))
    )
    (comp (ref "D349")
      (value "THIRD")
      (footprint "eagle-import:LED-0603")
      (libsource (lib "eagle-import") (part "SparkFun-LED_LED0603"))
    )
    (comp (ref "D350")
      (value "THIRD")
      (footprint "eagle-import:LED-0603")
      (libsource (lib "eagle-import") (part "SparkFun-LED_LED0603"))
    )
    (comp (ref "D351")
      (value "THIRD")
      (footprint "eagle-import:LED-0603")
      (libsource (lib "eagle-import") (part "SparkFun-LED_LED0603"))
    )
    (comp (ref "D352")
      (value "THIRD")
      (footprint "eagle-import:LED-0603")
      (libsource (lib "eagle-import") (part "SparkFun-LED_LED0603"))
    )
    (comp (ref "D353")
      (value "THIRD")
      (footprint "eagle-import:LED-0603")
      (libsource (lib "eagle-import") (part "SparkFun-LED_LED0603"))
    )
    (comp (ref "D354")
      (value "THIRD")
      (footprint "eagle-import:LED-0603")
      (libsource (lib "eagle-import") (part "SparkFun-LED_LED0603"))
    )
    (comp (ref "D355")
      (value "THIRD")
      (footprint "eagle-import:LED-0603")
      (libsource (lib "eagle-import") (part "SparkFun-LED_LED0603"))
    )
    (comp (ref "D356")
      (value "THIRD")
      (footprint "eagle-import:LED-0603")
      (libsource (lib "eagle-import") (part "SparkFun-LED_LED0603"))
    )
    (comp (ref "D357")
      (value "THIRD")
      (footprint "eagle-import:LED-0603")
      (libsource (lib "eagle-import") (part "SparkFun-LED_LED0603"))
    )
    (comp (ref "D358")
      (value "THIRD")
      (footprint "eagle-import:LED-0603")
      (libsource (lib "eagle-import") (part "SparkFun-LED_LED0603"))
    )
    (comp (ref "D359")
      (value "THIRD")
      (footprint "eagle-import:LED-0603")
      (libsource (lib "eagle-import") (part "SparkFun-LED_LED0603"))
    )
    (comp (ref "D408")
      (value "RED")
      (footprint "eagle-import:LED-0603")
      (libsource (lib "eagle-import") (part "LED0603"))
    )
    (comp (ref "D422")
      (value "BLUE")
      (footprint "eagle-import:LED-0603")
      (libsource (lib "eagle-import") (part "LED0603"))
    )
    (comp (ref "J002")
      (value "M04PTH")
      (footprint "eagle-import:1X04")
      (libsource (lib "eagle-import") (part "M04PTH"))
    )
    (comp (ref "J003")
      (value "M06SIP")
      (footprint "eagle-import:1X06")
      (libsource (lib "eagle-import") (part "M06SIP"))
    )
    (comp (ref "J501")
      (value "GP-2106")
      (footprint "eagle-import:GP-2106")
      (libsource (lib "eagle-import") (part "GP-2106"))
    )
    (comp (ref "JP1")
      (value "STANDOFF")
      (footprint "eagle-import:STANDOFF")
      (libsource (lib "eagle-import") (part "STANDOFF"))
    )
    (comp (ref "JP2")
      (value "STANDOFF")
      (footprint "eagle-import:STANDOFF")
      (libsource (lib "eagle-import") (part "STANDOFF"))
    )
    (comp (ref "JP3")
      (value "STANDOFF")
      (footprint "eagle-import:STANDOFF")
      (libsource (lib "eagle-import") (part "STANDOFF"))
    )
    (comp (ref "JP4")
      (value "STANDOFF")
      (footprint "eagle-import:STANDOFF")
      (libsource (lib "eagle-import") (part "STANDOFF"))
    )
    (comp (ref "Q501")
      (value "SSM6N58NU")
      (footprint "eagle-import:UDFN6")
      (libsource (lib "eagle-import") (part "SSM6N58NU"))
    )
    (comp (ref "Q502")
      (value "SSM6N58NU")
      (footprint "eagle-import:UDFN6")
      (libsource (lib "eagle-import") (part "SSM6N58NU"))
    )
    (comp (ref "R1")
      (value "47")
      (footprint "eagle-import:CRA04")
      (libsource (lib "eagle-import") (part "RP404"))
    )
    (comp (ref "R2")
      (value "47")
      (footprint "eagle-import:CRA04")
      (libsource (lib "eagle-import") (part "RP404"))
    )
    (comp (ref "R3")
      (value "47")
      (footprint "eagle-import:CRA04")
      (libsource (lib "eagle-import") (part "RP404"))
    )
    (comp (ref "R4")
      (value "47")
      (footprint "eagle-import:CRA04")
      (libsource (lib "eagle-import") (part "RP404"))
    )
    (comp (ref "R403")
      (value "22")
      (footprint "eagle-import:CRA02")
      (libsource (lib "eagle-import") (part "RP2EXB24V"))
    )
    (comp (ref "R413")
      (value "10k")
      (footprint "eagle-import:CRA02")
      (libsource (lib "eagle-import") (part "RP2EXB24V"))
    )
    (comp (ref "R422")
      (value "680")
      (footprint "eagle-import:CRA02")
      (libsource (lib "eagle-import") (part "RP2EXB24V"))
    )
    (comp (ref "R501")
      (value "10k")
      (footprint "eagle-import:CRA04")
      (fields (field (name "DIGIKEY") "CRA4S810KCT-ND"))
      (libsource (lib "eagle-import") (part "RP404"))
    )
    (comp (ref "R502")
      (value "10k")
      (footprint "eagle-import:CRA04")
      (fields (field (name "DIGIKEY") "CRA4S810KCT-ND"))
      (libsource (lib "eagle-import") (part "RP404"))
    )
    (comp (ref "S429")
      (value "B3U-1000P")
      (footprint "eagle-import:B3U-1000P")
      (libsource (lib "eagle-import") (part "B3U-1000P"))
    )
    (comp (ref "U401")
      (value "ATMEGA32U4TQFP")
      (footprint "eagle-import:SPARKFUN-DIGITALIC_TQFP44")
      (libsource (lib "eagle-import") (part "ATMEGA32U4TQFP"))
    )
    (comp (ref "U501")
      (value "5319 1.8V")
      (footprint "eagle-import:SOT-23-5")
      (libsource (lib "eagle-import") (part "MIC5319D5"))
    )
    (comp (ref "Y401")
      (value "16MHz")
      (footprint "eagle-import:CRYSTAL_SMD")
      (libsource (lib "eagle-import") (part "TSX-3225"))
    )
  )
  (nets
    (net (code "1") (name "/1PPS_I") (class "Default")
      (node (ref "J501") (pin "1PPS") (pinfunction "1PPS_1PPS") (pintype "bidirectional"))
      (node (ref "Q502") (pin "4") (pinfunction "S_4") (pintype "passive"))
      (node (ref "R502") (pin "2") (pinfunction "1_2") (pintype "passive"))
    )
    (net (code "2") (name "/AT_RX") (class "Default")
      (node (ref "Q501") (pin "3") (pinfunction "D_3") (pintype "passive"))
      (node (ref "R501") (pin "1") (pinfunction "1_1") (pintype "passive"))
      (node (ref "U401") (pin "20") (pinfunction "PD2(RX)_20") (pintype "bidirectional"))
    )
    (net (code "3") (name "/AT_TX") (class "Default")
      (node (ref "Q501") (pin "6") (pinfunction "D_6") (pintype "passive"))
      (node (ref "R501") (pin "4") (pinfunction "1_4") (pintype "passive"))
      (node (ref "U401") (pin "21") (pinfunction "PD3(TX)_21") (pintype "bidirectional"))
    )
    (net (code "4") (name "/MISO") (class "Default")
      (node (ref "J003") (pin "5") (pinfunction "5_5") (pintype "passive"))
      (node (ref "U401") (pin "11") (pinfunction "PB3(MISO)_11") (pintype "bidirectional"))
    )
    (net (code "5") (name "/MOSI") (class "Default")
      (node (ref "J003") (pin "6") (pinfunction "6_6") (pintype "passive"))
      (node (ref "U401") (pin "10") (pinfunction "PB2(MOSI)_10") (pintype "bidirectional"))
    )
    (net (code "6") (name "/ONOFF") (class "Default")
      (node (ref "Q502") (pin "6") (pinfunction "D_6") (pintype "passive"))
      (node (ref "R502") (pin "1") (pinfunction "1_1") (pintype "passive"))
      (node (ref "U401") (pin "26") (pinfunction "PD6(ADC9)_26") (pintype "bidirectional"))
    )
    (net (code "7") (name "/ONOFF_I") (class "Default")
      (node (ref "J501") (pin "ONOFF") (pinfunction "ONOFF_ONOFF") (pintype "bidirectional"))
      (node (ref "Q502") (pin "1") (pinfunction "S_1") (pintype "passive"))
      (node (ref "R502") (pin "3") (pinfunction "1_3") (pintype "passive"))
    )
    (net (code "8") (name "/P01") (class "Default")
      (node (ref "R1") (pin "1") (pinfunction "1_1") (pintype "passive"))
      (node (ref "U401") (pin "12") (pinfunction "PB7_12") (pintype "bidirectional"))
    )
    (net (code "9") (name "/P02") (class "Default")
      (node (ref "R1") (pin "2") (pinfunction "1_2") (pintype "passive"))
      (node (ref "U401") (pin "25") (pinfunction "PD4(ADC8)_25") (pintype "bidirectional"))
    )
    (net (code "10") (name "/P03") (class "Default")
      (node (ref "R1") (pin "3") (pinfunction "1_3") (pintype "passive"))
      (node (ref "U401") (pin "30") (pinfunction "PB6(ADC13)_30") (pintype "bidirectional"))
    )
    (net (code "11") (name "/P04") (class "Default")
      (node (ref "R1") (pin "4") (pinfunction "1_4") (pintype "passive"))
      (node (ref "U401") (pin "29") (pinfunction "PB5(ADC12)_29") (pintype "bidirectional"))
    )
    (net (code "12") (name "/P05") (class "Default")
      (node (ref "R2") (pin "1") (pinfunction "1_1") (pintype "passive"))
      (node (ref "U401") (pin "28") (pinfunction "PB4(ADC11)_28") (pintype "bidirectional"))
    )
    (net (code "13") (name "/P06") (class "Default")
      (node (ref "R2") (pin "2") (pinfunction "1_2") (pintype "passive"))
      (node (ref "U401") (pin "1") (pinfunction "PE6_1") (pintype "bidirectional"))
    )
    (net (code "14") (name "/P07") (class "Default")
      (node (ref "R2") (pin "3") (pinfunction "1_3") (pintype "passive"))
      (node (ref "U401") (pin "27") (pinfunction "PD7(ADC10)_27") (pintype "bidirectional"))
    )
    (net (code "15") (name "/P08") (class "Default")
      (node (ref "R2") (pin "4") (pinfunction "1_4") (pintype "passive"))
      (node (ref "U401") (pin "31") (pinfunction "PC6_31") (pintype "bidirectional"))
    )
    (net (code "16") (name "/P09") (class "Default")
      (node (ref "R3") (pin "1") (pinfunction "1_1") (pintype "passive"))
      (node (ref "U401") (pin "18") (pinfunction "PD0(SCL)_18") (pintype "bidirectional"))
    )
    (net (code "17") (name "/P10") (class "Default")
      (node (ref "R3") (pin "2") (pinfunction "1_2") (pintype "passive"))
      (node (ref "U401") (pin "41") (pinfunction "PF0(ADC0)_41") (pintype "bidirectional"))
    )
    (net (code "18") (name "/P11") (class "Default")
      (node (ref "R3") (pin "3") (pinfunction "1_3") (pintype "passive"))
      (node (ref "U401") (pin "40") (pinfunction "PF1(ADC1)_40") (pintype "bidirectional"))
    )
    (net (code "19") (name "/P12") (class "Default")
      (node (ref "R3") (pin "4") (pinfunction "1_4") (pintype "passive"))
      (node (ref "U401") (pin "39") (pinfunction "PF4(ADC4)_39") (pintype "bidirectional"))
    )
    (net (code "20") (name "/P13") (class "Default")
      (node (ref "R4") (pin "1") (pinfunction "1_1") (pintype "passive"))
      (node (ref "U401") (pin "38") (pinfunction "PF5(ADC5)_38") (pintype "bidirectional"))
    )
    (net (code "21") (name "/P14") (class "Default")
      (node (ref "R4") (pin "2") (pinfunction "1_2") (pintype "passive"))
      (node (ref "U401") (pin "37") (pinfunction "PF6(ADC6)_37") (pintype "bidirectional"))
    )
    (net (code "22") (name "/P15") (class "Default")
      (node (ref "R4") (pin "3") (pinfunction "1_3") (pintype "passive"))
      (node (ref "U401") (pin "36") (pinfunction "PF7(ADC7)_36") (pintype "bidirectional"))
    )
    (net (code "23") (name "/P16") (class "Default")
      (node (ref "R4") (pin "4") (pinfunction "1_4") (pintype "passive"))
      (node (ref "U401") (pin "32") (pinfunction "PC7_32") (pintype "bidirectional"))
    )
    (net (code "24") (name "/PPS") (class "Default")
      (node (ref "Q502") (pin "3") (pinfunction "D_3") (pintype "passive"))
      (node (ref "R502") (pin "4") (pinfunction "1_4") (pintype "passive"))
      (node (ref "U401") (pin "19") (pinfunction "PD1(SDA)_19") (pintype "bidirectional"))
    )
    (net (code "25") (name "/Q01") (class "Default")
      (node (ref "D000") (pin "C") (pinfunction "C_C") (pintype "passive"))
      (node (ref "D015") (pin "C") (pinfunction "C_C") (pintype "passive"))
      (node (ref "D029") (pin "C") (pinfunction "C_C") (pintype "passive"))
      (node (ref "D042") (pin "C") (pinfunction "C_C") (pintype "passive"))
      (node (ref "D054") (pin "C") (pinfunction "C_C") (pintype "passive"))
      (node (ref "D105") (pin "C") (pinfunction "C_C") (pintype "passive"))
      (node (ref "D115") (pin "C") (pinfunction "C_C") (pintype "passive"))
      (node (ref "D124") (pin "C") (pinfunction "C_C") (pintype "passive"))
      (node (ref "D132") (pin "C") (pinfunction "C_C") (pintype "passive"))
      (node (ref "D139") (pin "C") (pinfunction "C_C") (pintype "passive"))
      (node (ref "D145") (pin "C") (pinfunction "C_C") (pintype "passive"))
      (node (ref "D150") (pin "C") (pinfunction "C_C") (pintype "passive"))
      (node (ref "D154") (pin "C") (pinfunction "C_C") (pintype "passive"))
      (node (ref "D157") (pin "C") (pinfunction "C_C") (pintype "passive"))
      (node (ref "D159") (pin "C") (pinfunction "C_C") (pintype "passive"))
      (node (ref "D200") (pin "A") (pinfunction "A_A") (pintype "passive"))
      (node (ref "D215") (pin "A") (pinfunction "A_A") (pintype "passive"))
      (node (ref "D229") (pin "A") (pinfunction "A_A") (pintype "passive"))
      (node (ref "D242") (pin "A") (pinfunction "A_A") (pintype "passive"))
      (node (ref "D254") (pin "A") (pinfunction "A_A") (pintype "passive"))
      (node (ref "D305") (pin "A") (pinfunction "A_A") (pintype "passive"))
      (node (ref "D315") (pin "A") (pinfunction "A_A") (pintype "passive"))
      (node (ref "D324") (pin "A") (pinfunction "A_A") (pintype "passive"))
      (node (ref "D332") (pin "A") (pinfunction "A_A") (pintype "passive"))
      (node (ref "D339") (pin "A") (pinfunction "A_A") (pintype "passive"))
      (node (ref "D345") (pin "A") (pinfunction "A_A") (pintype "passive"))
      (node (ref "D350") (pin "A") (pinfunction "A_A") (pintype "passive"))
      (node (ref "D354") (pin "A") (pinfunction "A_A") (pintype "passive"))
      (node (ref "D357") (pin "A") (pinfunction "A_A") (pintype "passive"))
      (node (ref "D359") (pin "A") (pinfunction "A_A") (pintype "passive"))
      (node (ref "R1") (pin "8") (pinfunction "2_8") (pintype "passive"))
    )
    (net (code "26") (name "/Q02") (class "Default")
      (node (ref "D000") (pin "A") (pinfunction "A_A") (pintype "passive"))
      (node (ref "D001") (pin "C") (pinfunction "C_C") (pintype "passive"))
      (node (ref "D016") (pin "C") (pinfunction "C_C") (pintype "passive"))
      (node (ref "D030") (pin "C") (pinfunction "C_C") (pintype "passive"))
      (node (ref "D043") (pin "C") (pinfunction "C_C") (pintype "passive"))
      (node (ref "D055") (pin "C") (pinfunction "C_C") (pintype "passive"))
      (node (ref "D106") (pin "C") (pinfunction "C_C") (pintype "passive"))
      (node (ref "D116") (pin "C") (pinfunction "C_C") (pintype "passive"))
      (node (ref "D125") (pin "C") (pinfunction "C_C") (pintype "passive"))
      (node (ref "D133") (pin "C") (pinfunction "C_C") (pintype "passive"))
      (node (ref "D140") (pin "C") (pinfunction "C_C") (pintype "passive"))
      (node (ref "D146") (pin "C") (pinfunction "C_C") (pintype "passive"))
      (node (ref "D151") (pin "C") (pinfunction "C_C") (pintype "passive"))
      (node (ref "D155") (pin "C") (pinfunction "C_C") (pintype "passive"))
      (node (ref "D158") (pin "C") (pinfunction "C_C") (pintype "passive"))
      (node (ref "D200") (pin "C") (pinfunction "C_C") (pintype "passive"))
      (node (ref "D201") (pin "A") (pinfunction "A_A") (pintype "passive"))
      (node (ref "D216") (pin "A") (pinfunction "A_A") (pintype "passive"))
      (node (ref "D230") (pin "A") (pinfunction "A_A") (pintype "passive"))
      (node (ref "D243") (pin "A") (pinfunction "A_A") (pintype "passive"))
      (node (ref "D255") (pin "A") (pinfunction "A_A") (pintype "passive"))
      (node (ref "D306") (pin "A") (pinfunction "A_A") (pintype "passive"))
      (node (ref "D316") (pin "A") (pinfunction "A_A") (pintype "passive"))
      (node (ref "D325") (pin "A") (pinfunction "A_A") (pintype "passive"))
      (node (ref "D333") (pin "A") (pinfunction "A_A") (pintype "passive"))
      (node (ref "D340") (pin "A") (pinfunction "A_A") (pintype "passive"))
      (node (ref "D346") (pin "A") (pinfunction "A_A") (pintype "passive"))
      (node (ref "D351") (pin "A") (pinfunction "A_A") (pintype "passive"))
      (node (ref "D355") (pin "A") (pinfunction "A_A") (pintype "passive"))
      (node (ref "D358") (pin "A") (pinfunction "A_A") (pintype "passive"))
      (node (ref "R1") (pin "7") (pinfunction "2_7") (pintype "passive"))
    )
    (net (code "27") (name "/Q03") (class "Default")
      (node (ref "D001") (pin "A") (pinfunction "A_A") (pintype "passive"))
      (node (ref "D002") (pin "C") (pinfunction "C_C") (pintype "passive"))
      (node (ref "D015") (pin "A") (pinfunction "A_A") (pintype "passive"))
      (node (ref "D017") (pin "C") (pinfunction "C_C") (pintype "passive"))
      (node (ref "D031") (pin "C") (pinfunction "C_C") (pintype "passive"))
      (node (ref "D044") (pin "C") (pinfunction "C_C") (pintype "passive"))
      (node (ref "D056") (pin "C") (pinfunction "C_C") (pintype "passive"))
      (node (ref "D107") (pin "C") (pinfunction "C_C") (pintype "passive"))
      (node (ref "D117") (pin "C") (pinfunction "C_C") (pintype "passive"))
      (node (ref "D126") (pin "C") (pinfunction "C_C") (pintype "passive"))
      (node (ref "D134") (pin "C") (pinfunction "C_C") (pintype "passive"))
      (node (ref "D141") (pin "C") (pinfunction "C_C") (pintype "passive"))
      (node (ref "D147") (pin "C") (pinfunction "C_C") (pintype "passive"))
      (node (ref "D152") (pin "C") (pinfunction "C_C") (pintype "passive"))
      (node (ref "D156") (pin "C") (pinfunction "C_C") (pintype "passive"))
      (node (ref "D201") (pin "C") (pinfunction "C_C") (pintype "passive"))
      (node (ref "D202") (pin "A") (pinfunction "A_A") (pintype "passive"))
      (node (ref "D215") (pin "C") (pinfunction "C_C") (pintype "passive"))
      (node (ref "D217") (pin "A") (pinfunction "A_A") (pintype "passive"))
      (node (ref "D231") (pin "A") (pinfunction "A_A") (pintype "passive"))
      (node (ref "D244") (pin "A") (pinfunction "A_A") (pintype "passive"))
      (node (ref "D256") (pin "A") (pinfunction "A_A") (pintype "passive"))
      (node (ref "D307") (pin "A") (pinfunction "A_A") (pintype "passive"))
      (node (ref "D317") (pin "A") (pinfunction "A_A") (pintype "passive"))
      (node (ref "D326") (pin "A") (pinfunction "A_A") (pintype "passive"))
      (node (ref "D334") (pin "A") (pinfunction "A_A") (pintype "passive"))
      (node (ref "D341") (pin "A") (pinfunction "A_A") (pintype "passive"))
      (node (ref "D347") (pin "A") (pinfunction "A_A") (pintype "passive"))
      (node (ref "D352") (pin "A") (pinfunction "A_A") (pintype "passive"))
      (node (ref "D356") (pin "A") (pinfunction "A_A") (pintype "passive"))
      (node (ref "R1") (pin "6") (pinfunction "2_6") (pintype "passive"))
    )
    (net (code "28") (name "/Q04") (class "Default")
      (node (ref "D002") (pin "A") (pinfunction "A_A") (pintype "passive"))
      (node (ref "D003") (pin "C") (pinfunction "C_C") (pintype "passive"))
      (node (ref "D016") (pin "A") (pinfunction "A_A") (pintype "passive"))
      (node (ref "D018") (pin "C") (pinfunction "C_C") (pintype "passive"))
      (node (ref "D029") (pin "A") (pinfunction "A_A") (pintype "passive"))
      (node (ref "D032") (pin "C") (pinfunction "C_C") (pintype "passive"))
      (node (ref "D045") (pin "C") (pinfunction "C_C") (pintype "passive"))
      (node (ref "D057") (pin "C") (pinfunction "C_C") (pintype "passive"))
      (node (ref "D108") (pin "C") (pinfunction "C_C") (pintype "passive"))
      (node (ref "D118") (pin "C") (pinfunction "C_C") (pintype "passive"))
      (node (ref "D127") (pin "C") (pinfunction "C_C") (pintype "passive"))
      (node (ref "D135") (pin "C") (pinfunction "C_C") (pintype "passive"))
      (node (ref "D142") (pin "C") (pinfunction "C_C") (pintype "passive"))
      (node (ref "D148") (pin "C") (pinfunction "C_C") (pintype "passive"))
      (node (ref "D153") (pin "C") (pinfunction "C_C") (pintype "passive"))
      (node (ref "D202") (pin "C") (pinfunction "C_C") (pintype "passive"))
      (node (ref "D203") (pin "A") (pinfunction "A_A") (pintype "passive"))
      (node (ref "D216") (pin "C") (pinfunction "C_C") (pintype "passive"))
      (node (ref "D218") (pin "A") (pinfunction "A_A") (pintype "passive"))
      (node (ref "D229") (pin "C") (pinfunction "C_C") (pintype "passive"))
      (node (ref "D232") (pin "A") (pinfunction "A_A") (pintype "passive"))
      (node (ref "D245") (pin "A") (pinfunction "A_A") (pintype "passive"))
      (node (ref "D257") (pin "A") (pinfunction "A_A") (pintype "passive"))
      (node (ref "D308") (pin "A") (pinfunction "A_A") (pintype "passive"))
      (node (ref "D318") (pin "A") (pinfunction "A_A") (pintype "passive"))
      (node (ref "D327") (pin "A") (pinfunction "A_A") (pintype "passive"))
      (node (ref "D335") (pin "A") (pinfunction "A_A") (pintype "passive"))
      (node (ref "D342") (pin "A") (pinfunction "A_A") (pintype "passive"))
      (node (ref "D348") (pin "A") (pinfunction "A_A") (pintype "passive"))
      (node (ref "D353") (pin "A") (pinfunction "A_A") (pintype "passive"))
      (node (ref "R1") (pin "5") (pinfunction "2_5") (pintype "passive"))
    )
    (net (code "29") (name "/Q05") (class "Default")
      (node (ref "D003") (pin "A") (pinfunction "A_A") (pintype "passive"))
      (node (ref "D004") (pin "C") (pinfunction "C_C") (pintype "passive"))
      (node (ref "D017") (pin "A") (pinfunction "A_A") (pintype "passive"))
      (node (ref "D019") (pin "C") (pinfunction "C_C") (pintype "passive"))
      (node (ref "D030") (pin "A") (pinfunction "A_A") (pintype "passive"))
      (node (ref "D033") (pin "C") (pinfunction "C_C") (pintype "passive"))
      (node (ref "D042") (pin "A") (pinfunction "A_A") (pintype "passive"))
      (node (ref "D046") (pin "C") (pinfunction "C_C") (pintype "passive"))
      (node (ref "D058") (pin "C") (pinfunction "C_C") (pintype "passive"))
      (node (ref "D109") (pin "C") (pinfunction "C_C") (pintype "passive"))
      (node (ref "D119") (pin "C") (pinfunction "C_C") (pintype "passive"))
      (node (ref "D128") (pin "C") (pinfunction "C_C") (pintype "passive"))
      (node (ref "D136") (pin "C") (pinfunction "C_C") (pintype "passive"))
      (node (ref "D143") (pin "C") (pinfunction "C_C") (pintype "passive"))
      (node (ref "D149") (pin "C") (pinfunction "C_C") (pintype "passive"))
      (node (ref "D203") (pin "C") (pinfunction "C_C") (pintype "passive"))
      (node (ref "D204") (pin "A") (pinfunction "A_A") (pintype "passive"))
      (node (ref "D217") (pin "C") (pinfunction "C_C") (pintype "passive"))
      (node (ref "D219") (pin "A") (pinfunction "A_A") (pintype "passive"))
      (node (ref "D230") (pin "C") (pinfunction "C_C") (pintype "passive"))
      (node (ref "D233") (pin "A") (pinfunction "A_A") (pintype "passive"))
      (node (ref "D242") (pin "C") (pinfunction "C_C") (pintype "passive"))
      (node (ref "D246") (pin "A") (pinfunction "A_A") (pintype "passive"))
      (node (ref "D258") (pin "A") (pinfunction "A_A") (pintype "passive"))
      (node (ref "D309") (pin "A") (pinfunction "A_A") (pintype "passive"))
      (node (ref "D319") (pin "A") (pinfunction "A_A") (pintype "passive"))
      (node (ref "D328") (pin "A") (pinfunction "A_A") (pintype "passive"))
      (node (ref "D336") (pin "A") (pinfunction "A_A") (pintype "passive"))
      (node (ref "D343") (pin "A") (pinfunction "A_A") (pintype "passive"))
      (node (ref "D349") (pin "A") (pinfunction "A_A") (pintype "passive"))
      (node (ref "R2") (pin "8") (pinfunction "2_8") (pintype "passive"))
    )
    (net (code "30") (name "/Q06") (class "Default")
      (node (ref "D004") (pin "A") (pinfunction "A_A") (pintype "passive"))
      (node (ref "D005") (pin "C") (pinfunction "C_C") (pintype "passive"))
      (node (ref "D018") (pin "A") (pinfunction "A_A") (pintype "passive"))
      (node (ref "D020") (pin "C") (pinfunction "C_C") (pintype "passive"))
      (node (ref "D031") (pin "A") (pinfunction "A_A") (pintype "passive"))
      (node (ref "D034") (pin "C") (pinfunction "C_C") (pintype "passive"))
      (node (ref "D043") (pin "A") (pinfunction "A_A") (pintype "passive"))
      (node (ref "D047") (pin "C") (pinfunction "C_C") (pintype "passive"))
      (node (ref "D054") (pin "A") (pinfunction "A_A") (pintype "passive"))
      (node (ref "D059") (pin "C") (pinfunction "C_C") (pintype "passive"))
      (node (ref "D110") (pin "C") (pinfunction "C_C") (pintype "passive"))
      (node (ref "D120") (pin "C") (pinfunction "C_C") (pintype "passive"))
      (node (ref "D129") (pin "C") (pinfunction "C_C") (pintype "passive"))
      (node (ref "D137") (pin "C") (pinfunction "C_C") (pintype "passive"))
      (node (ref "D144") (pin "C") (pinfunction "C_C") (pintype "passive"))
      (node (ref "D204") (pin "C") (pinfunction "C_C") (pintype "passive"))
      (node (ref "D205") (pin "A") (pinfunction "A_A") (pintype "passive"))
      (node (ref "D218") (pin "C") (pinfunction "C_C") (pintype "passive"))
      (node (ref "D220") (pin "A") (pinfunction "A_A") (pintype "passive"))
      (node (ref "D231") (pin "C") (pinfunction "C_C") (pintype "passive"))
      (node (ref "D234") (pin "A") (pinfunction "A_A") (pintype "passive"))
      (node (ref "D243") (pin "C") (pinfunction "C_C") (pintype "passive"))
      (node (ref "D247") (pin "A") (pinfunction "A_A") (pintype "passive"))
      (node (ref "D254") (pin "C") (pinfunction "C_C") (pintype "passive"))
      (node (ref "D259") (pin "A") (pinfunction "A_A") (pintype "passive"))
      (node (ref "D310") (pin "A") (pinfunction "A_A") (pintype "passive"))
      (node (ref "D320") (pin "A") (pinfunction "A_A") (pintype "passive"))
      (node (ref "D329") (pin "A") (pinfunction "A_A") (pintype "passive"))
      (node (ref "D337") (pin "A") (pinfunction "A_A") (pintype "passive"))
      (node (ref "D344") (pin "A") (pinfunction "A_A") (pintype "passive"))
      (node (ref "R2") (pin "7") (pinfunction "2_7") (pintype "passive"))
    )
    (net (code "31") (name "/Q07") (class "Default")
      (node (ref "D005") (pin "A") (pinfunction "A_A") (pintype "passive"))
      (node (ref "D006") (pin "C") (pinfunction "C_C") (pintype "passive"))
      (node (ref "D019") (pin "A") (pinfunction "A_A") (pintype "passive"))
      (node (ref "D021") (pin "C") (pinfunction "C_C") (pintype "passive"))
      (node (ref "D032") (pin "A") (pinfunction "A_A") (pintype "passive"))
      (node (ref "D035") (pin "C") (pinfunction "C_C") (pintype "passive"))
      (node (ref "D044") (pin "A") (pinfunction "A_A") (pintype "passive"))
      (node (ref "D048") (pin "C") (pinfunction "C_C") (pintype "passive"))
      (node (ref "D055") (pin "A") (pinfunction "A_A") (pintype "passive"))
      (node (ref "D100") (pin "C") (pinfunction "C_C") (pintype "passive"))
      (node (ref "D105") (pin "A") (pinfunction "A_A") (pintype "passive"))
      (node (ref "D111") (pin "C") (pinfunction "C_C") (pintype "passive"))
      (node (ref "D121") (pin "C") (pinfunction "C_C") (pintype "passive"))
      (node (ref "D130") (pin "C") (pinfunction "C_C") (pintype "passive"))
      (node (ref "D138") (pin "C") (pinfunction "C_C") (pintype "passive"))
      (node (ref "D205") (pin "C") (pinfunction "C_C") (pintype "passive"))
      (node (ref "D206") (pin "A") (pinfunction "A_A") (pintype "passive"))
      (node (ref "D219") (pin "C") (pinfunction "C_C") (pintype "passive"))
      (node (ref "D221") (pin "A") (pinfunction "A_A") (pintype "passive"))
      (node (ref "D232") (pin "C") (pinfunction "C_C") (pintype "passive"))
      (node (ref "D235") (pin "A") (pinfunction "A_A") (pintype "passive"))
      (node (ref "D244") (pin "C") (pinfunction "C_C") (pintype "passive"))
      (node (ref "D248") (pin "A") (pinfunction "A_A") (pintype "passive"))
      (node (ref "D255") (pin "C") (pinfunction "C_C") (pintype "passive"))
      (node (ref "D300") (pin "A") (pinfunction "A_A") (pintype "passive"))
      (node (ref "D305") (pin "C") (pinfunction "C_C") (pintype "passive"))
      (node (ref "D311") (pin "A") (pinfunction "A_A") (pintype "passive"))
      (node (ref "D321") (pin "A") (pinfunction "A_A") (pintype "passive"))
      (node (ref "D330") (pin "A") (pinfunction "A_A") (pintype "passive"))
      (node (ref "D338") (pin "A") (pinfunction "A_A") (pintype "passive"))
      (node (ref "R2") (pin "6") (pinfunction "2_6") (pintype "passive"))
    )
    (net (code "32") (name "/Q08") (class "Default")
      (node (ref "D006") (pin "A") (pinfunction "A_A") (pintype "passive"))
      (node (ref "D007") (pin "C") (pinfunction "C_C") (pintype "passive"))
      (node (ref "D020") (pin "A") (pinfunction "A_A") (pintype "passive"))
      (node (ref "D022") (pin "C") (pinfunction "C_C") (pintype "passive"))
      (node (ref "D033") (pin "A") (pinfunction "A_A") (pintype "passive"))
      (node (ref "D036") (pin "C") (pinfunction "C_C") (pintype "passive"))
      (node (ref "D045") (pin "A") (pinfunction "A_A") (pintype "passive"))
      (node (ref "D049") (pin "C") (pinfunction "C_C") (pintype "passive"))
      (node (ref "D056") (pin "A") (pinfunction "A_A") (pintype "passive"))
      (node (ref "D101") (pin "C") (pinfunction "C_C") (pintype "passive"))
      (node (ref "D106") (pin "A") (pinfunction "A_A") (pintype "passive"))
      (node (ref "D112") (pin "C") (pinfunction "C_C") (pintype "passive"))
      (node (ref "D115") (pin "A") (pinfunction "A_A") (pintype "passive"))
      (node (ref "D122") (pin "C") (pinfunction "C_C") (pintype "passive"))
      (node (ref "D131") (pin "C") (pinfunction "C_C") (pintype "passive"))
      (node (ref "D206") (pin "C") (pinfunction "C_C") (pintype "passive"))
      (node (ref "D207") (pin "A") (pinfunction "A_A") (pintype "passive"))
      (node (ref "D220") (pin "C") (pinfunction "C_C") (pintype "passive"))
      (node (ref "D222") (pin "A") (pinfunction "A_A") (pintype "passive"))
      (node (ref "D233") (pin "C") (pinfunction "C_C") (pintype "passive"))
      (node (ref "D236") (pin "A") (pinfunction "A_A") (pintype "passive"))
      (node (ref "D245") (pin "C") (pinfunction "C_C") (pintype "passive"))
      (node (ref "D249") (pin "A") (pinfunction "A_A") (pintype "passive"))
      (node (ref "D256") (pin "C") (pinfunction "C_C") (pintype "passive"))
      (node (ref "D301") (pin "A") (pinfunction "A_A") (pintype "passive"))
      (node (ref "D306") (pin "C") (pinfunction "C_C") (pintype "passive"))
      (node (ref "D312") (pin "A") (pinfunction "A_A") (pintype "passive"))
      (node (ref "D315") (pin "C") (pinfunction "C_C") (pintype "passive"))
      (node (ref "D322") (pin "A") (pinfunction "A_A") (pintype "passive"))
      (node (ref "D331") (pin "A") (pinfunction "A_A") (pintype "passive"))
      (node (ref "R2") (pin "5") (pinfunction "2_5") (pintype "passive"))
    )
    (net (code "33") (name "/Q09") (class "Default")
      (node (ref "D007") (pin "A") (pinfunction "A_A") (pintype "passive"))
      (node (ref "D008") (pin "C") (pinfunction "C_C") (pintype "passive"))
      (node (ref "D021") (pin "A") (pinfunction "A_A") (pintype "passive"))
      (node (ref "D023") (pin "C") (pinfunction "C_C") (pintype "passive"))
      (node (ref "D034") (pin "A") (pinfunction "A_A") (pintype "passive"))
      (node (ref "D037") (pin "C") (pinfunction "C_C") (pintype "passive"))
      (node (ref "D046") (pin "A") (pinfunction "A_A") (pintype "passive"))
      (node (ref "D050") (pin "C") (pinfunction "C_C") (pintype "passive"))
      (node (ref "D057") (pin "A") (pinfunction "A_A") (pintype "passive"))
      (node (ref "D102") (pin "C") (pinfunction "C_C") (pintype "passive"))
      (node (ref "D107") (pin "A") (pinfunction "A_A") (pintype "passive"))
      (node (ref "D113") (pin "C") (pinfunction "C_C") (pintype "passive"))
      (node (ref "D116") (pin "A") (pinfunction "A_A") (pintype "passive"))
      (node (ref "D123") (pin "C") (pinfunction "C_C") (pintype "passive"))
      (node (ref "D124") (pin "A") (pinfunction "A_A") (pintype "passive"))
      (node (ref "D207") (pin "C") (pinfunction "C_C") (pintype "passive"))
      (node (ref "D208") (pin "A") (pinfunction "A_A") (pintype "passive"))
      (node (ref "D221") (pin "C") (pinfunction "C_C") (pintype "passive"))
      (node (ref "D223") (pin "A") (pinfunction "A_A") (pintype "passive"))
      (node (ref "D234") (pin "C") (pinfunction "C_C") (pintype "passive"))
      (node (ref "D237") (pin "A") (pinfunction "A_A") (pintype "passive"))
      (node (ref "D246") (pin "C") (pinfunction "C_C") (pintype "passive"))
      (node (ref "D250") (pin "A") (pinfunction "A_A") (pintype "passive"))
      (node (ref "D257") (pin "C") (pinfunction "C_C") (pintype "passive"))
      (node (ref "D302") (pin "A") (pinfunction "A_A") (pintype "passive"))
      (node (ref "D307") (pin "C") (pinfunction "C_C") (pintype "passive"))
      (node (ref "D313") (pin "A") (pinfunction "A_A") (pintype "passive"))
      (node (ref "D316") (pin "C") (pinfunction "C_C") (pintype "passive"))
      (node (ref "D323") (pin "A") (pinfunction "A_A") (pintype "passive"))
      (node (ref "D324") (pin "C") (pinfunction "C_C") (pintype "passive"))
      (node (ref "R3") (pin "8") (pinfunction "2_8") (pintype "passive"))
    )
    (net (code "34") (name "/Q10") (class "Default")
      (node (ref "D008") (pin "A") (pinfunction "A_A") (pintype "passive"))
      (node (ref "D009") (pin "C") (pinfunction "C_C") (pintype "passive"))
      (node (ref "D022") (pin "A") (pinfunction "A_A") (pintype "passive"))
      (node (ref "D024") (pin "C") (pinfunction "C_C") (pintype "passive"))
      (node (ref "D035") (pin "A") (pinfunction "A_A") (pintype "passive"))
      (node (ref "D038") (pin "C") (pinfunction "C_C") (pintype "passive"))
      (node (ref "D047") (pin "A") (pinfunction "A_A") (pintype "passive"))
      (node (ref "D051") (pin "C") (pinfunction "C_C") (pintype "passive"))
      (node (ref "D058") (pin "A") (pinfunction "A_A") (pintype "passive"))
      (node (ref "D103") (pin "C") (pinfunction "C_C") (pintype "passive"))
      (node (ref "D108") (pin "A") (pinfunction "A_A") (pintype "passive"))
      (node (ref "D114") (pin "C") (pinfunction "C_C") (pintype "passive"))
      (node (ref "D117") (pin "A") (pinfunction "A_A") (pintype "passive"))
      (node (ref "D125") (pin "A") (pinfunction "A_A") (pintype "passive"))
      (node (ref "D132") (pin "A") (pinfunction "A_A") (pintype "passive"))
      (node (ref "D208") (pin "C") (pinfunction "C_C") (pintype "passive"))
      (node (ref "D209") (pin "A") (pinfunction "A_A") (pintype "passive"))
      (node (ref "D222") (pin "C") (pinfunction "C_C") (pintype "passive"))
      (node (ref "D224") (pin "A") (pinfunction "A_A") (pintype "passive"))
      (node (ref "D235") (pin "C") (pinfunction "C_C") (pintype "passive"))
      (node (ref "D238") (pin "A") (pinfunction "A_A") (pintype "passive"))
      (node (ref "D247") (pin "C") (pinfunction "C_C") (pintype "passive"))
      (node (ref "D251") (pin "A") (pinfunction "A_A") (pintype "passive"))
      (node (ref "D258") (pin "C") (pinfunction "C_C") (pintype "passive"))
      (node (ref "D303") (pin "A") (pinfunction "A_A") (pintype "passive"))
      (node (ref "D308") (pin "C") (pinfunction "C_C") (pintype "passive"))
      (node (ref "D314") (pin "A") (pinfunction "A_A") (pintype "passive"))
      (node (ref "D317") (pin "C") (pinfunction "C_C") (pintype "passive"))
      (node (ref "D325") (pin "C") (pinfunction "C_C") (pintype "passive"))
      (node (ref "D332") (pin "C") (pinfunction "C_C") (pintype "passive"))
      (node (ref "R3") (pin "7") (pinfunction "2_7") (pintype "passive"))
    )
    (net (code "35") (name "/Q11") (class "Default")
      (node (ref "D009") (pin "A") (pinfunction "A_A") (pintype "passive"))
      (node (ref "D010") (pin "C") (pinfunction "C_C") (pintype "passive"))
      (node (ref "D023") (pin "A") (pinfunction "A_A") (pintype "passive"))
      (node (ref "D025") (pin "C") (pinfunction "C_C") (pintype "passive"))
      (node (ref "D036") (pin "A") (pinfunction "A_A") (pintype "passive"))
      (node (ref "D039") (pin "C") (pinfunction "C_C") (pintype "passive"))
      (node (ref "D048") (pin "A") (pinfunction "A_A") (pintype "passive"))
      (node (ref "D052") (pin "C") (pinfunction "C_C") (pintype "passive"))
      (node (ref "D059") (pin "A") (pinfunction "A_A") (pintype "passive"))
      (node (ref "D104") (pin "C") (pinfunction "C_C") (pintype "passive"))
      (node (ref "D109") (pin "A") (pinfunction "A_A") (pintype "passive"))
      (node (ref "D118") (pin "A") (pinfunction "A_A") (pintype "passive"))
      (node (ref "D126") (pin "A") (pinfunction "A_A") (pintype "passive"))
      (node (ref "D133") (pin "A") (pinfunction "A_A") (pintype "passive"))
      (node (ref "D139") (pin "A") (pinfunction "A_A") (pintype "passive"))
      (node (ref "D209") (pin "C") (pinfunction "C_C") (pintype "passive"))
      (node (ref "D210") (pin "A") (pinfunction "A_A") (pintype "passive"))
      (node (ref "D223") (pin "C") (pinfunction "C_C") (pintype "passive"))
      (node (ref "D225") (pin "A") (pinfunction "A_A") (pintype "passive"))
      (node (ref "D236") (pin "C") (pinfunction "C_C") (pintype "passive"))
      (node (ref "D239") (pin "A") (pinfunction "A_A") (pintype "passive"))
      (node (ref "D248") (pin "C") (pinfunction "C_C") (pintype "passive"))
      (node (ref "D252") (pin "A") (pinfunction "A_A") (pintype "passive"))
      (node (ref "D259") (pin "C") (pinfunction "C_C") (pintype "passive"))
      (node (ref "D304") (pin "A") (pinfunction "A_A") (pintype "passive"))
      (node (ref "D309") (pin "C") (pinfunction "C_C") (pintype "passive"))
      (node (ref "D318") (pin "C") (pinfunction "C_C") (pintype "passive"))
      (node (ref "D326") (pin "C") (pinfunction "C_C") (pintype "passive"))
      (node (ref "D333") (pin "C") (pinfunction "C_C") (pintype "passive"))
      (node (ref "D339") (pin "C") (pinfunction "C_C") (pintype "passive"))
      (node (ref "R3") (pin "6") (pinfunction "2_6") (pintype "passive"))
    )
    (net (code "36") (name "/Q12") (class "Default")
      (node (ref "D010") (pin "A") (pinfunction "A_A") (pintype "passive"))
      (node (ref "D011") (pin "C") (pinfunction "C_C") (pintype "passive"))
      (node (ref "D024") (pin "A") (pinfunction "A_A") (pintype "passive"))
      (node (ref "D026") (pin "C") (pinfunction "C_C") (pintype "passive"))
      (node (ref "D037") (pin "A") (pinfunction "A_A") (pintype "passive"))
      (node (ref "D040") (pin "C") (pinfunction "C_C") (pintype "passive"))
      (node (ref "D049") (pin "A") (pinfunction "A_A") (pintype "passive"))
      (node (ref "D053") (pin "C") (pinfunction "C_C") (pintype "passive"))
      (node (ref "D100") (pin "A") (pinfunction "A_A") (pintype "passive"))
      (node (ref "D110") (pin "A") (pinfunction "A_A") (pintype "passive"))
      (node (ref "D119") (pin "A") (pinfunction "A_A") (pintype "passive"))
      (node (ref "D127") (pin "A") (pinfunction "A_A") (pintype "passive"))
      (node (ref "D134") (pin "A") (pinfunction "A_A") (pintype "passive"))
      (node (ref "D140") (pin "A") (pinfunction "A_A") (pintype "passive"))
      (node (ref "D145") (pin "A") (pinfunction "A_A") (pintype "passive"))
      (node (ref "D210") (pin "C") (pinfunction "C_C") (pintype "passive"))
      (node (ref "D211") (pin "A") (pinfunction "A_A") (pintype "passive"))
      (node (ref "D224") (pin "C") (pinfunction "C_C") (pintype "passive"))
      (node (ref "D226") (pin "A") (pinfunction "A_A") (pintype "passive"))
      (node (ref "D237") (pin "C") (pinfunction "C_C") (pintype "passive"))
      (node (ref "D240") (pin "A") (pinfunction "A_A") (pintype "passive"))
      (node (ref "D249") (pin "C") (pinfunction "C_C") (pintype "passive"))
      (node (ref "D253") (pin "A") (pinfunction "A_A") (pintype "passive"))
      (node (ref "D300") (pin "C") (pinfunction "C_C") (pintype "passive"))
      (node (ref "D310") (pin "C") (pinfunction "C_C") (pintype "passive"))
      (node (ref "D319") (pin "C") (pinfunction "C_C") (pintype "passive"))
      (node (ref "D327") (pin "C") (pinfunction "C_C") (pintype "passive"))
      (node (ref "D334") (pin "C") (pinfunction "C_C") (pintype "passive"))
      (node (ref "D340") (pin "C") (pinfunction "C_C") (pintype "passive"))
      (node (ref "D345") (pin "C") (pinfunction "C_C") (pintype "passive"))
      (node (ref "R3") (pin "5") (pinfunction "2_5") (pintype "passive"))
    )
    (net (code "37") (name "/Q13") (class "Default")
      (node (ref "D011") (pin "A") (pinfunction "A_A") (pintype "passive"))
      (node (ref "D012") (pin "C") (pinfunction "C_C") (pintype "passive"))
      (node (ref "D025") (pin "A") (pinfunction "A_A") (pintype "passive"))
      (node (ref "D027") (pin "C") (pinfunction "C_C") (pintype "passive"))
      (node (ref "D038") (pin "A") (pinfunction "A_A") (pintype "passive"))
      (node (ref "D041") (pin "C") (pinfunction "C_C") (pintype "passive"))
      (node (ref "D050") (pin "A") (pinfunction "A_A") (pintype "passive"))
      (node (ref "D101") (pin "A") (pinfunction "A_A") (pintype "passive"))
      (node (ref "D111") (pin "A") (pinfunction "A_A") (pintype "passive"))
      (node (ref "D120") (pin "A") (pinfunction "A_A") (pintype "passive"))
      (node (ref "D128") (pin "A") (pinfunction "A_A") (pintype "passive"))
      (node (ref "D135") (pin "A") (pinfunction "A_A") (pintype "passive"))
      (node (ref "D141") (pin "A") (pinfunction "A_A") (pintype "passive"))
      (node (ref "D146") (pin "A") (pinfunction "A_A") (pintype "passive"))
      (node (ref "D150") (pin "A") (pinfunction "A_A") (pintype "passive"))
      (node (ref "D211") (pin "C") (pinfunction "C_C") (pintype "passive"))
      (node (ref "D212") (pin "A") (pinfunction "A_A") (pintype "passive"))
      (node (ref "D225") (pin "C") (pinfunction "C_C") (pintype "passive"))
      (node (ref "D227") (pin "A") (pinfunction "A_A") (pintype "passive"))
      (node (ref "D238") (pin "C") (pinfunction "C_C") (pintype "passive"))
      (node (ref "D241") (pin "A") (pinfunction "A_A") (pintype "passive"))
      (node (ref "D250") (pin "C") (pinfunction "C_C") (pintype "passive"))
      (node (ref "D301") (pin "C") (pinfunction "C_C") (pintype "passive"))
      (node (ref "D311") (pin "C") (pinfunction "C_C") (pintype "passive"))
      (node (ref "D320") (pin "C") (pinfunction "C_C") (pintype "passive"))
      (node (ref "D328") (pin "C") (pinfunction "C_C") (pintype "passive"))
      (node (ref "D335") (pin "C") (pinfunction "C_C") (pintype "passive"))
      (node (ref "D341") (pin "C") (pinfunction "C_C") (pintype "passive"))
      (node (ref "D346") (pin "C") (pinfunction "C_C") (pintype "passive"))
      (node (ref "D350") (pin "C") (pinfunction "C_C") (pintype "passive"))
      (node (ref "R4") (pin "8") (pinfunction "2_8") (pintype "passive"))
    )
    (net (code "38") (name "/Q14") (class "Default")
      (node (ref "D012") (pin "A") (pinfunction "A_A") (pintype "passive"))
      (node (ref "D013") (pin "C") (pinfunction "C_C") (pintype "passive"))
      (node (ref "D026") (pin "A") (pinfunction "A_A") (pintype "passive"))
      (node (ref "D028") (pin "C") (pinfunction "C_C") (pintype "passive"))
      (node (ref "D039") (pin "A") (pinfunction "A_A") (pintype "passive"))
      (node (ref "D051") (pin "A") (pinfunction "A_A") (pintype "passive"))
      (node (ref "D102") (pin "A") (pinfunction "A_A") (pintype "passive"))
      (node (ref "D112") (pin "A") (pinfunction "A_A") (pintype "passive"))
      (node (ref "D121") (pin "A") (pinfunction "A_A") (pintype "passive"))
      (node (ref "D129") (pin "A") (pinfunction "A_A") (pintype "passive"))
      (node (ref "D136") (pin "A") (pinfunction "A_A") (pintype "passive"))
      (node (ref "D142") (pin "A") (pinfunction "A_A") (pintype "passive"))
      (node (ref "D147") (pin "A") (pinfunction "A_A") (pintype "passive"))
      (node (ref "D151") (pin "A") (pinfunction "A_A") (pintype "passive"))
      (node (ref "D154") (pin "A") (pinfunction "A_A") (pintype "passive"))
      (node (ref "D212") (pin "C") (pinfunction "C_C") (pintype "passive"))
      (node (ref "D213") (pin "A") (pinfunction "A_A") (pintype "passive"))
      (node (ref "D226") (pin "C") (pinfunction "C_C") (pintype "passive"))
      (node (ref "D228") (pin "A") (pinfunction "A_A") (pintype "passive"))
      (node (ref "D239") (pin "C") (pinfunction "C_C") (pintype "passive"))
      (node (ref "D251") (pin "C") (pinfunction "C_C") (pintype "passive"))
      (node (ref "D302") (pin "C") (pinfunction "C_C") (pintype "passive"))
      (node (ref "D312") (pin "C") (pinfunction "C_C") (pintype "passive"))
      (node (ref "D321") (pin "C") (pinfunction "C_C") (pintype "passive"))
      (node (ref "D329") (pin "C") (pinfunction "C_C") (pintype "passive"))
      (node (ref "D336") (pin "C") (pinfunction "C_C") (pintype "passive"))
      (node (ref "D342") (pin "C") (pinfunction "C_C") (pintype "passive"))
      (node (ref "D347") (pin "C") (pinfunction "C_C") (pintype "passive"))
      (node (ref "D351") (pin "C") (pinfunction "C_C") (pintype "passive"))
      (node (ref "D354") (pin "C") (pinfunction "C_C") (pintype "passive"))
      (node (ref "R4") (pin "7") (pinfunction "2_7") (pintype "passive"))
    )
    (net (code "39") (name "/Q15") (class "Default")
      (node (ref "D013") (pin "A") (pinfunction "A_A") (pintype "passive"))
      (node (ref "D014") (pin "C") (pinfunction "C_C") (pintype "passive"))
      (node (ref "D027") (pin "A") (pinfunction "A_A") (pintype "passive"))
      (node (ref "D040") (pin "A") (pinfunction "A_A") (pintype "passive"))
      (node (ref "D052") (pin "A") (pinfunction "A_A") (pintype "passive"))
      (node (ref "D103") (pin "A") (pinfunction "A_A") (pintype "passive"))
      (node (ref "D113") (pin "A") (pinfunction "A_A") (pintype "passive"))
      (node (ref "D122") (pin "A") (pinfunction "A_A") (pintype "passive"))
      (node (ref "D130") (pin "A") (pinfunction "A_A") (pintype "passive"))
      (node (ref "D137") (pin "A") (pinfunction "A_A") (pintype "passive"))
      (node (ref "D143") (pin "A") (pinfunction "A_A") (pintype "passive"))
      (node (ref "D148") (pin "A") (pinfunction "A_A") (pintype "passive"))
      (node (ref "D152") (pin "A") (pinfunction "A_A") (pintype "passive"))
      (node (ref "D155") (pin "A") (pinfunction "A_A") (pintype "passive"))
      (node (ref "D157") (pin "A") (pinfunction "A_A") (pintype "passive"))
      (node (ref "D213") (pin "C") (pinfunction "C_C") (pintype "passive"))
      (node (ref "D214") (pin "A") (pinfunction "A_A") (pintype "passive"))
      (node (ref "D227") (pin "C") (pinfunction "C_C") (pintype "passive"))
      (node (ref "D240") (pin "C") (pinfunction "C_C") (pintype "passive"))
      (node (ref "D252") (pin "C") (pinfunction "C_C") (pintype "passive"))
      (node (ref "D303") (pin "C") (pinfunction "C_C") (pintype "passive"))
      (node (ref "D313") (pin "C") (pinfunction "C_C") (pintype "passive"))
      (node (ref "D322") (pin "C") (pinfunction "C_C") (pintype "passive"))
      (node (ref "D330") (pin "C") (pinfunction "C_C") (pintype "passive"))
      (node (ref "D337") (pin "C") (pinfunction "C_C") (pintype "passive"))
      (node (ref "D343") (pin "C") (pinfunction "C_C") (pintype "passive"))
      (node (ref "D348") (pin "C") (pinfunction "C_C") (pintype "passive"))
      (node (ref "D352") (pin "C") (pinfunction "C_C") (pintype "passive"))
      (node (ref "D355") (pin "C") (pinfunction "C_C") (pintype "passive"))
      (node (ref "D357") (pin "C") (pinfunction "C_C") (pintype "passive"))
      (node (ref "R4") (pin "6") (pinfunction "2_6") (pintype "passive"))
    )
    (net (code "40") (name "/Q16") (class "Default")
      (node (ref "D014") (pin "A") (pinfunction "A_A") (pintype "passive"))
      (node (ref "D028") (pin "A") (pinfunction "A_A") (pintype "passive"))
      (node (ref "D041") (pin "A") (pinfunction "A_A") (pintype "passive"))
      (node (ref "D053") (pin "A") (pinfunction "A_A") (pintype "passive"))
      (node (ref "D104") (pin "A") (pinfunction "A_A") (pintype "passive"))
      (node (ref "D114") (pin "A") (pinfunction "A_A") (pintype "passive"))
      (node (ref "D123") (pin "A") (pinfunction "A_A") (pintype "passive"))
      (node (ref "D131") (pin "A") (pinfunction "A_A") (pintype "passive"))
      (node (ref "D138") (pin "A") (pinfunction "A_A") (pintype "passive"))
      (node (ref "D144") (pin "A") (pinfunction "A_A") (pintype "passive"))
      (node (ref "D149") (pin "A") (pinfunction "A_A") (pintype "passive"))
      (node (ref "D153") (pin "A") (pinfunction "A_A") (pintype "passive"))
      (node (ref "D156") (pin "A") (pinfunction "A_A") (pintype "passive"))
      (node (ref "D158") (pin "A") (pinfunction "A_A") (pintype "passive"))
      (node (ref "D159") (pin "A") (pinfunction "A_A") (pintype "passive"))
      (node (ref "D214") (pin "C") (pinfunction "C_C") (pintype "passive"))
      (node (ref "D228") (pin "C") (pinfunction "C_C") (pintype "passive"))
      (node (ref "D241") (pin "C") (pinfunction "C_C") (pintype "passive"))
      (node (ref "D253") (pin "C") (pinfunction "C_C") (pintype "passive"))
      (node (ref "D304") (pin "C") (pinfunction "C_C") (pintype "passive"))
      (node (ref "D314") (pin "C") (pinfunction "C_C") (pintype "passive"))
      (node (ref "D323") (pin "C") (pinfunction "C_C") (pintype "passive"))
      (node (ref "D331") (pin "C") (pinfunction "C_C") (pintype "passive"))
      (node (ref "D338") (pin "C") (pinfunction "C_C") (pintype "passive"))
      (node (ref "D344") (pin "C") (pinfunction "C_C") (pintype "passive"))
      (node (ref "D349") (pin "C") (pinfunction "C_C") (pintype "passive"))
      (node (ref "D353") (pin "C") (pinfunction "C_C") (pintype "passive"))
      (node (ref "D356") (pin "C") (pinfunction "C_C") (pintype "passive"))
      (node (ref "D358") (pin "C") (pinfunction "C_C") (pintype "passive"))
      (node (ref "D359") (pin "C") (pinfunction "C_C") (pintype "passive"))
      (node (ref "R4") (pin "5") (pinfunction "2_5") (pintype "passive"))
    )
    (net (code "41") (name "/RESET") (class "Default")
      (node (ref "J003") (pin "1") (pinfunction "1_1") (pintype "passive"))
      (node (ref "R413") (pin "1") (pinfunction "1_1") (pintype "passive"))
      (node (ref "S429") (pin "P$2") (pinfunction "2_P$2") (pintype "bidirectional"))
      (node (ref "U401") (pin "13") (pinfunction "~{RESET}_13") (pintype "bidirectional"))
    )
    (net (code "42") (name "/RXLED") (class "Default")
      (node (ref "D408") (pin "C") (pinfunction "C_C") (pintype "passive"))
      (node (ref "U401") (pin "8") (pinfunction "PB0(SS)_8") (pintype "bidirectional"))
    )
    (net (code "43") (name "/RX_I") (class "Default")
      (node (ref "J501") (pin "RX") (pinfunction "RX_RX") (pintype "bidirectional"))
      (node (ref "Q501") (pin "1") (pinfunction "S_1") (pintype "passive"))
      (node (ref "R501") (pin "2") (pinfunction "1_2") (pintype "passive"))
    )
    (net (code "44") (name "/SCK") (class "Default")
      (node (ref "J003") (pin "4") (pinfunction "4_4") (pintype "passive"))
      (node (ref "U401") (pin "9") (pinfunction "PB1(SCK)_9") (pintype "bidirectional"))
    )
    (net (code "45") (name "/TXLED") (class "Default")
      (node (ref "D422") (pin "C") (pinfunction "C_C") (pintype "passive"))
      (node (ref "U401") (pin "22") (pinfunction "PD5_22") (pintype "bidirectional"))
    )
    (net (code "46") (name "/TX_O") (class "Default")
      (node (ref "J501") (pin "TX") (pinfunction "TX_TX") (pintype "bidirectional"))
      (node (ref "Q501") (pin "4") (pinfunction "S_4") (pintype "passive"))
      (node (ref "R501") (pin "3") (pinfunction "1_3") (pintype "passive"))
    )
    (net (code "47") (name "/USBD+") (class "Default")
      (node (ref "J002") (pin "1") (pinfunction "1_1") (pintype "passive"))
      (node (ref "R403") (pin "2") (pinfunction "1_2") (pintype "passive"))
    )
    (net (code "48") (name "/USBD-") (class "Default")
      (node (ref "J002") (pin "2") (pinfunction "2_2") (pintype "passive"))
      (node (ref "R403") (pin "1") (pinfunction "1_1") (pintype "passive"))
    )
    (net (code "49") (name "1.8V") (class "Default")
      (node (ref "C505") (pin "1") (pinfunction "1_1") (pintype "passive"))
      (node (ref "J501") (pin "VCC") (pinfunction "VCC_VCC") (pintype "bidirectional"))
      (node (ref "Q501") (pin "2") (pinfunction "G_2") (pintype "passive"))
      (node (ref "Q501") (pin "5") (pinfunction "G_5") (pintype "passive"))
      (node (ref "Q502") (pin "2") (pinfunction "G_2") (pintype "passive"))
      (node (ref "Q502") (pin "5") (pinfunction "G_5") (pintype "passive"))
      (node (ref "R501") (pin "6") (pinfunction "2_6") (pintype "passive"))
      (node (ref "R501") (pin "7") (pinfunction "2_7") (pintype "passive"))
      (node (ref "R502") (pin "6") (pinfunction "2_6") (pintype "passive"))
      (node (ref "R502") (pin "7") (pinfunction "2_7") (pintype "passive"))
      (node (ref "U501") (pin "5") (pinfunction "VOUT_5") (pintype "bidirectional"))
    )
    (net (code "50") (name "GND") (class "Default")
      (node (ref "C010") (pin "2") (pinfunction "2_2") (pintype "passive"))
      (node (ref "C402") (pin "1") (pinfunction "1_1") (pintype "passive"))
      (node (ref "C406") (pin "1") (pinfunction "1_1") (pintype "passive"))
      (node (ref "C416") (pin "1") (pinfunction "1_1") (pintype "passive"))
      (node (ref "C417") (pin "1") (pinfunction "1_1") (pintype "passive"))
      (node (ref "C420") (pin "2") (pinfunction "2_2") (pintype "passive"))
      (node (ref "C501") (pin "2") (pinfunction "2_2") (pintype "passive"))
      (node (ref "C504") (pin "2") (pinfunction "2_2") (pintype "passive"))
      (node (ref "C505") (pin "2") (pinfunction "2_2") (pintype "passive"))
      (node (ref "J002") (pin "4") (pinfunction "4_4") (pintype "passive"))
      (node (ref "J003") (pin "3") (pinfunction "3_3") (pintype "passive"))
      (node (ref "J501") (pin "GND") (pinfunction "GND_GND") (pintype "bidirectional"))
      (node (ref "JP1") (pin "P$1") (pinfunction "P$1_P$1") (pintype "bidirectional"))
      (node (ref "JP2") (pin "P$1") (pinfunction "P$1_P$1") (pintype "bidirectional"))
      (node (ref "JP3") (pin "P$1") (pinfunction "P$1_P$1") (pintype "bidirectional"))
      (node (ref "JP4") (pin "P$1") (pinfunction "P$1_P$1") (pintype "bidirectional"))
      (node (ref "R413") (pin "2") (pinfunction "1_2") (pintype "passive"))
      (node (ref "S429") (pin "P$1") (pinfunction "1_P$1") (pintype "bidirectional"))
      (node (ref "U401") (pin "15") (pinfunction "GND_15") (pintype "bidirectional"))
      (node (ref "U401") (pin "23") (pinfunction "GND_23") (pintype "bidirectional"))
      (node (ref "U401") (pin "35") (pinfunction "GND_35") (pintype "bidirectional"))
      (node (ref "U401") (pin "43") (pinfunction "GND_43") (pintype "bidirectional"))
      (node (ref "U401") (pin "5") (pinfunction "UGND_5") (pintype "bidirectional"))
      (node (ref "U501") (pin "2") (pinfunction "GND_2") (pintype "bidirectional"))
      (node (ref "Y401") (pin "2") (pinfunction "GND_2") (pintype "passive"))
      (node (ref "Y401") (pin "4") (pinfunction "GND_4") (pintype "passive"))
    )
    (net (code "51") (name "Net-(D422-PadA)") (class "Default")
      (node (ref "D422") (pin "A") (pinfunction "A_A") (pintype "passive"))
      (node (ref "R422") (pin "1") (pinfunction "1_1") (pintype "passive"))
    )
    (net (code "52") (name "Net-(R403A-2)") (class "Default")
      (node (ref "R403") (pin "4") (pinfunction "2_4") (pintype "passive"))
      (node (ref "U401") (pin "3") (pinfunction "D-_3") (pintype "bidirectional"))
    )
    (net (code "53") (name "Net-(R403B-2)") (class "Default")
      (node (ref "R403") (pin "3") (pinfunction "2_3") (pintype "passive"))
      (node (ref "U401") (pin "4") (pinfunction "D+_4") (pintype "bidirectional"))
    )
    (net (code "54") (name "Net-(R413B-2)") (class "Default")
      (node (ref "R413") (pin "3") (pinfunction "2_3") (pintype "passive"))
      (node (ref "U401") (pin "33") (pinfunction "PE2/~{HWB}_33") (pintype "bidirectional"))
    )
    (net (code "55") (name "Net-(R422B-1)") (class "Default")
      (node (ref "D408") (pin "A") (pinfunction "A_A") (pintype "passive"))
      (node (ref "R422") (pin "2") (pinfunction "1_2") (pintype "passive"))
    )
    (net (code "56") (name "Net-(U401-AREF)") (class "Default")
      (node (ref "C420") (pin "1") (pinfunction "1_1") (pintype "passive"))
      (node (ref "U401") (pin "42") (pinfunction "AREF_42") (pintype "bidirectional"))
    )
    (net (code "57") (name "Net-(U401-UCAP)") (class "Default")
      (node (ref "C406") (pin "2") (pinfunction "2_2") (pintype "passive"))
      (node (ref "U401") (pin "6") (pinfunction "UCAP_6") (pintype "bidirectional"))
    )
    (net (code "58") (name "Net-(U401-XTAL1)") (class "Default")
      (node (ref "C417") (pin "2") (pinfunction "2_2") (pintype "passive"))
      (node (ref "U401") (pin "17") (pinfunction "XTAL1_17") (pintype "bidirectional"))
      (node (ref "Y401") (pin "1") (pinfunction "1_1") (pintype "passive"))
    )
    (net (code "59") (name "Net-(U401-XTAL2)") (class "Default")
      (node (ref "C416") (pin "2") (pinfunction "2_2") (pintype "passive"))
      (node (ref "U401") (pin "16") (pinfunction "XTAL2_16") (pintype "bidirectional"))
      (node (ref "Y401") (pin "3") (pinfunction "2_3") (pintype "passive"))
    )
    (net (code "60") (name "Net-(U501-BYP)") (class "Default")
      (node (ref "C504") (pin "1") (pinfunction "1_1") (pintype "passive"))
      (node (ref "U501") (pin "4") (pinfunction "BYP_4") (pintype "bidirectional"))
    )
    (net (code "61") (name "VCC") (class "Default")
      (node (ref "C010") (pin "1") (pinfunction "1_1") (pintype "passive"))
      (node (ref "C402") (pin "2") (pinfunction "2_2") (pintype "passive"))
      (node (ref "C501") (pin "1") (pinfunction "1_1") (pintype "passive"))
      (node (ref "J002") (pin "3") (pinfunction "3_3") (pintype "passive"))
      (node (ref "J003") (pin "2") (pinfunction "2_2") (pintype "passive"))
      (node (ref "R413") (pin "4") (pinfunction "2_4") (pintype "passive"))
      (node (ref "R422") (pin "3") (pinfunction "2_3") (pintype "passive"))
      (node (ref "R422") (pin "4") (pinfunction "2_4") (pintype "passive"))
      (node (ref "R501") (pin "5") (pinfunction "2_5") (pintype "passive"))
      (node (ref "R501") (pin "8") (pinfunction "2_8") (pintype "passive"))
      (node (ref "R502") (pin "5") (pinfunction "2_5") (pintype "passive"))
      (node (ref "R502") (pin "8") (pinfunction "2_8") (pintype "passive"))
      (node (ref "U401") (pin "14") (pinfunction "VCC_14") (pintype "bidirectional"))
      (node (ref "U401") (pin "2") (pinfunction "UVCC_2") (pintype "bidirectional"))
      (node (ref "U401") (pin "24") (pinfunction "AVCC_24") (pintype "bidirectional"))
      (node (ref "U401") (pin "34") (pinfunction "VCC_34") (pintype "bidirectional"))
      (node (ref "U401") (pin "44") (pinfunction "AVCC_44") (pintype "bidirectional"))
      (node (ref "U401") (pin "7") (pinfunction "VBUS_7") (pintype "bidirectional"))
      (node (ref "U501") (pin "1") (pinfunction "VIN_1") (pintype "bidirectional"))
      (node (ref "U501") (pin "3") (pinfunction "EN_3") (pintype "bidirectional"))
    )
  )
)
